# PP-Rev1.net
KiCad netlist of a schematic drawn in EAGLE
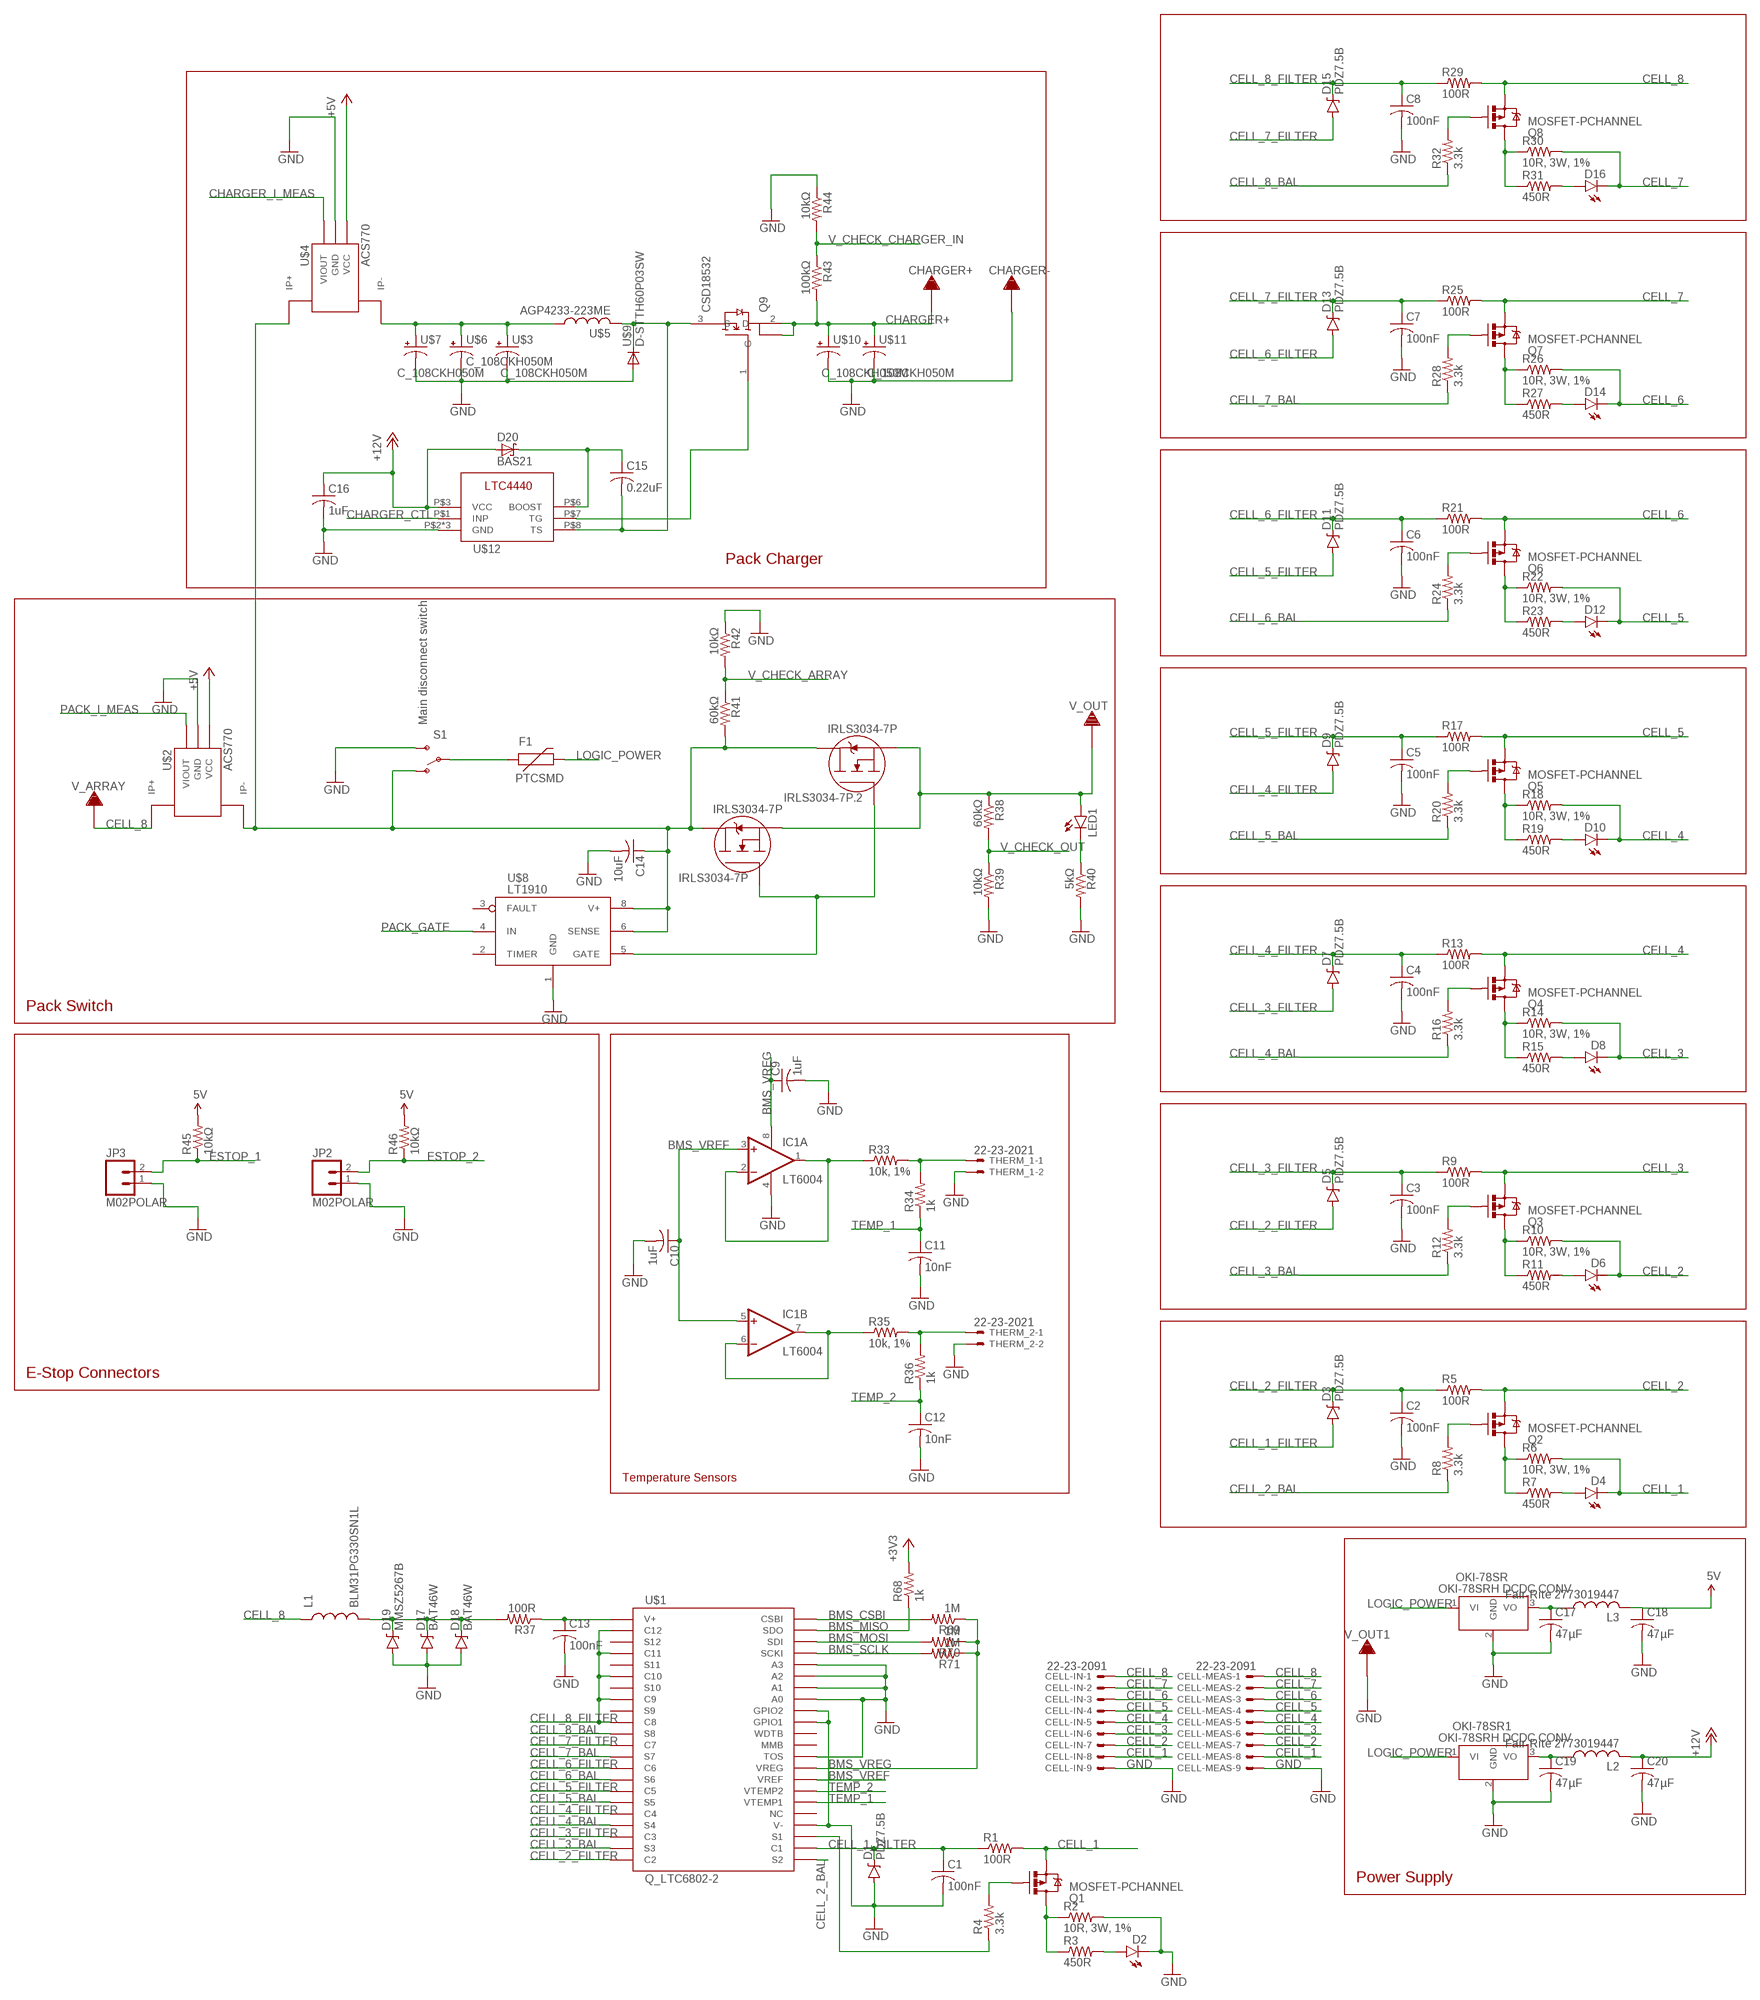
[diagram p0: schematic, sheet 1, part 1 of 2]
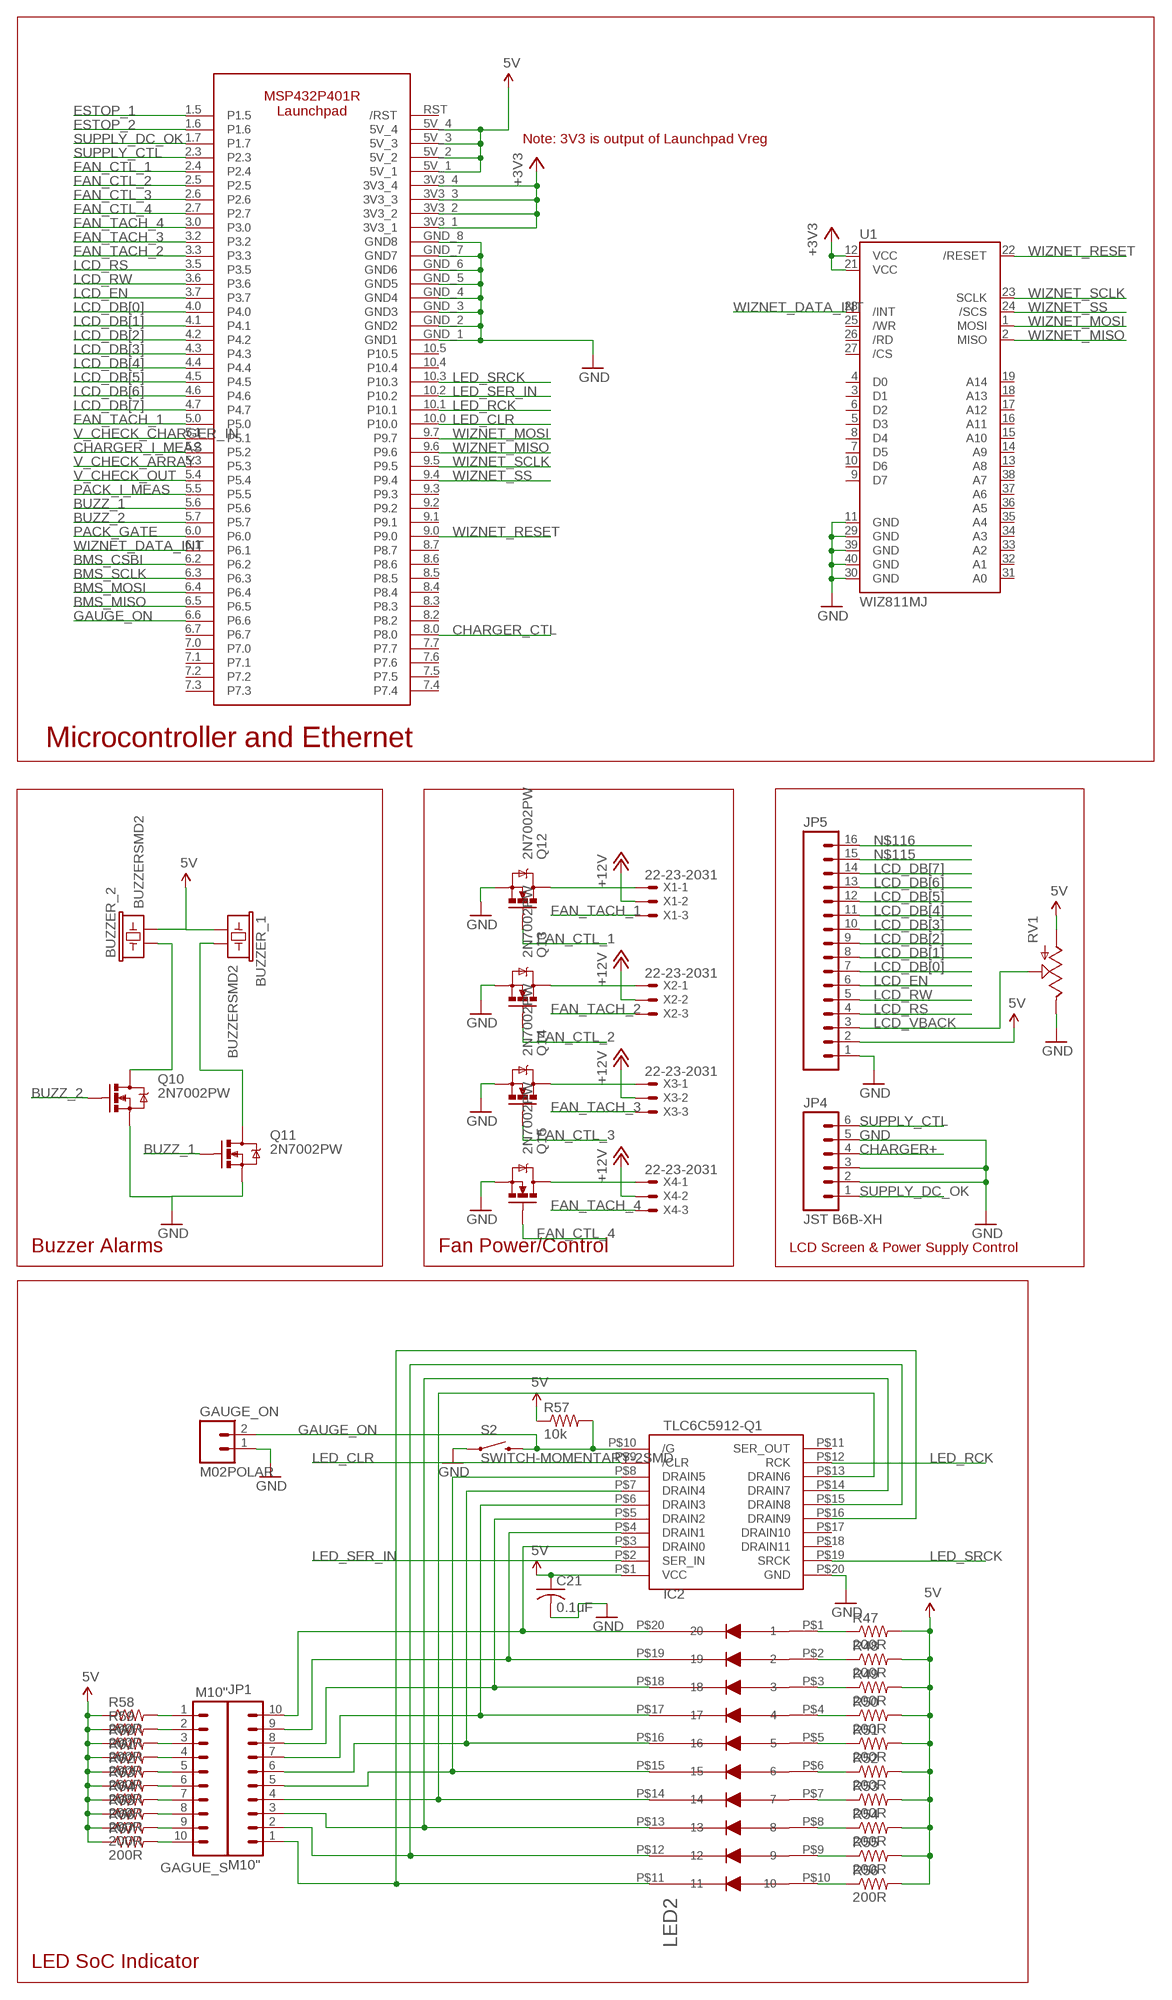
[diagram p1: schematic, sheet 1, part 2 of 2]

(export (version "E")
  (design (tool "Eeschema 10.0.6"))
  (components
    (comp (ref "BUZZER_1")
      (value "BUZZERSMD2")
      (footprint "eagle-import:BUZZER-CCV")
      (libsource (lib "eagle-import") (part "BUZZERSMD2"))
    )
    (comp (ref "BUZZER_2")
      (value "BUZZERSMD2")
      (footprint "eagle-import:BUZZER-CCV")
      (libsource (lib "eagle-import") (part "BUZZERSMD2"))
    )
    (comp (ref "C1")
      (value "100nF")
      (footprint "eagle-import:C1206")
      (libsource (lib "eagle-import") (part "C-USC1206"))
    )
    (comp (ref "C2")
      (value "100nF")
      (footprint "eagle-import:C1206")
      (libsource (lib "eagle-import") (part "C-USC1206"))
    )
    (comp (ref "C3")
      (value "100nF")
      (footprint "eagle-import:C1206")
      (libsource (lib "eagle-import") (part "C-USC1206"))
    )
    (comp (ref "C4")
      (value "100nF")
      (footprint "eagle-import:C1206")
      (libsource (lib "eagle-import") (part "C-USC1206"))
    )
    (comp (ref "C5")
      (value "100nF")
      (footprint "eagle-import:C1206")
      (libsource (lib "eagle-import") (part "C-USC1206"))
    )
    (comp (ref "C6")
      (value "100nF")
      (footprint "eagle-import:C1206")
      (libsource (lib "eagle-import") (part "C-USC1206"))
    )
    (comp (ref "C7")
      (value "100nF")
      (footprint "eagle-import:C1206")
      (libsource (lib "eagle-import") (part "C-USC1206"))
    )
    (comp (ref "C8")
      (value "100nF")
      (footprint "eagle-import:C1206")
      (libsource (lib "eagle-import") (part "C-USC1206"))
    )
    (comp (ref "C9")
      (value "1uF")
      (footprint "eagle-import:C1206")
      (libsource (lib "eagle-import") (part "C-USC1206"))
    )
    (comp (ref "C10")
      (value "1uF")
      (footprint "eagle-import:C1206")
      (libsource (lib "eagle-import") (part "C-USC1206"))
    )
    (comp (ref "C11")
      (value "10nF")
      (footprint "eagle-import:C1206")
      (libsource (lib "eagle-import") (part "C-USC1206"))
    )
    (comp (ref "C12")
      (value "10nF")
      (footprint "eagle-import:C1206")
      (libsource (lib "eagle-import") (part "C-USC1206"))
    )
    (comp (ref "C13")
      (value "100nF")
      (footprint "eagle-import:C1206")
      (libsource (lib "eagle-import") (part "C-USC1206"))
    )
    (comp (ref "C14")
      (value "10uF")
      (footprint "eagle-import:C1206")
      (libsource (lib "eagle-import") (part "C-USC1206"))
    )
    (comp (ref "C15")
      (value "0.22uF")
      (footprint "eagle-import:C1206")
      (libsource (lib "eagle-import") (part "C-USC1206"))
    )
    (comp (ref "C16")
      (value "1uF")
      (footprint "eagle-import:C1206")
      (libsource (lib "eagle-import") (part "C-USC1206"))
    )
    (comp (ref "C17")
      (value "47µF")
      (footprint "eagle-import:C1206")
      (libsource (lib "eagle-import") (part "resistor_C-USC1206"))
    )
    (comp (ref "C18")
      (value "47µF")
      (footprint "eagle-import:C1206")
      (libsource (lib "eagle-import") (part "resistor_C-USC1206"))
    )
    (comp (ref "C19")
      (value "47µF")
      (footprint "eagle-import:C1206")
      (libsource (lib "eagle-import") (part "resistor_C-USC1206"))
    )
    (comp (ref "C20")
      (value "47µF")
      (footprint "eagle-import:C1206")
      (libsource (lib "eagle-import") (part "resistor_C-USC1206"))
    )
    (comp (ref "C21")
      (value "0.1uF")
      (footprint "eagle-import:C1206")
      (libsource (lib "eagle-import") (part "resistor_C-USC1206"))
    )
    (comp (ref "CELL-IN")
      (value "22-23-2091")
      (footprint "eagle-import:22-23-2091")
      (fields (field (name "MF") "MOLEX"))
      (libsource (lib "eagle-import") (part "22-23-2091"))
    )
    (comp (ref "CELL-MEAS")
      (value "22-23-2091")
      (footprint "eagle-import:22-23-2091")
      (fields (field (name "MF") "MOLEX"))
      (libsource (lib "eagle-import") (part "22-23-2091"))
    )
    (comp (ref "CHARGER+")
      (value "TERMINAL_HOLE")
      (footprint "eagle-import:LARGE_TERMINAL_HOLE")
      (libsource (lib "eagle-import") (part "TERMINAL_HOLE"))
    )
    (comp (ref "CHARGER-")
      (value "TERMINAL_HOLE")
      (footprint "eagle-import:LARGE_TERMINAL_HOLE")
      (libsource (lib "eagle-import") (part "TERMINAL_HOLE"))
    )
    (comp (ref "D1")
      (value "PDZ7.5B")
      (footprint "eagle-import:SOD-323")
      (libsource (lib "eagle-import") (part "DIODE-ZENER5.6V"))
    )
    (comp (ref "D2")
      (value "LED1206")
      (footprint "eagle-import:LED-1206")
      (libsource (lib "eagle-import") (part "LED1206"))
    )
    (comp (ref "D3")
      (value "PDZ7.5B")
      (footprint "eagle-import:SOD-323")
      (libsource (lib "eagle-import") (part "DIODE-ZENER5.6V"))
    )
    (comp (ref "D4")
      (value "LED1206")
      (footprint "eagle-import:LED-1206")
      (libsource (lib "eagle-import") (part "LED1206"))
    )
    (comp (ref "D5")
      (value "PDZ7.5B")
      (footprint "eagle-import:SOD-323")
      (libsource (lib "eagle-import") (part "DIODE-ZENER5.6V"))
    )
    (comp (ref "D6")
      (value "LED1206")
      (footprint "eagle-import:LED-1206")
      (libsource (lib "eagle-import") (part "LED1206"))
    )
    (comp (ref "D7")
      (value "PDZ7.5B")
      (footprint "eagle-import:SOD-323")
      (libsource (lib "eagle-import") (part "DIODE-ZENER5.6V"))
    )
    (comp (ref "D8")
      (value "LED1206")
      (footprint "eagle-import:LED-1206")
      (libsource (lib "eagle-import") (part "LED1206"))
    )
    (comp (ref "D9")
      (value "PDZ7.5B")
      (footprint "eagle-import:SOD-323")
      (libsource (lib "eagle-import") (part "DIODE-ZENER5.6V"))
    )
    (comp (ref "D10")
      (value "LED1206")
      (footprint "eagle-import:LED-1206")
      (libsource (lib "eagle-import") (part "LED1206"))
    )
    (comp (ref "D11")
      (value "PDZ7.5B")
      (footprint "eagle-import:SOD-323")
      (libsource (lib "eagle-import") (part "DIODE-ZENER5.6V"))
    )
    (comp (ref "D12")
      (value "LED1206")
      (footprint "eagle-import:LED-1206")
      (libsource (lib "eagle-import") (part "LED1206"))
    )
    (comp (ref "D13")
      (value "PDZ7.5B")
      (footprint "eagle-import:SOD-323")
      (libsource (lib "eagle-import") (part "DIODE-ZENER5.6V"))
    )
    (comp (ref "D14")
      (value "LED1206")
      (footprint "eagle-import:LED-1206")
      (libsource (lib "eagle-import") (part "LED1206"))
    )
    (comp (ref "D15")
      (value "PDZ7.5B")
      (footprint "eagle-import:SOD-323")
      (libsource (lib "eagle-import") (part "DIODE-ZENER5.6V"))
    )
    (comp (ref "D16")
      (value "LED1206")
      (footprint "eagle-import:LED-1206")
      (libsource (lib "eagle-import") (part "LED1206"))
    )
    (comp (ref "D17")
      (value "BAT46W")
      (footprint "eagle-import:SOD-123")
      (libsource (lib "eagle-import") (part "DIODE-ZENER16V"))
    )
    (comp (ref "D18")
      (value "BAT46W")
      (footprint "eagle-import:SOD-123")
      (libsource (lib "eagle-import") (part "DIODE-ZENER16V"))
    )
    (comp (ref "D19")
      (value "MMSZ5267B")
      (footprint "eagle-import:SOD-123")
      (libsource (lib "eagle-import") (part "DIODE-ZENER16V"))
    )
    (comp (ref "D20")
      (value "BAS21")
      (footprint "eagle-import:SOT23")
      (libsource (lib "eagle-import") (part "BAS40"))
    )
    (comp (ref "F1")
      (value "PTCSMD")
      (footprint "eagle-import:PTC-1206")
      (libsource (lib "eagle-import") (part "PTCSMD"))
    )
    (comp (ref "GAGUE_S")
      (value "M10\"")
      (footprint "eagle-import:1X10")
      (libsource (lib "eagle-import") (part "M10{dblquote}"))
    )
    (comp (ref "GAUGE_ON")
      (value "M02POLAR")
      (footprint "eagle-import:MOLEX-1X2")
      (libsource (lib "eagle-import") (part "M02POLAR"))
    )
    (comp (ref "IC1")
      (value "LT6004")
      (footprint "eagle-import:MSOP08")
      (libsource (lib "eagle-import") (part "OPA2E345"))
    )
    (comp (ref "IC2")
      (value "TLC6C5912-Q1")
      (footprint "eagle-import:SOIC-20")
      (libsource (lib "eagle-import") (part "TLC6C5912-Q1"))
    )
    (comp (ref "IRLS3034-7P")
      (value "IRLS3034-7P")
      (footprint "eagle-import:D2PAK-7")
      (libsource (lib "eagle-import") (part "IRLS3034-7P"))
    )
    (comp (ref "IRLS3034-7P.2")
      (value "IRLS3034-7P")
      (footprint "eagle-import:D2PAK-7")
      (libsource (lib "eagle-import") (part "IRLS3034-7P"))
    )
    (comp (ref "JP1")
      (value "M10\"")
      (footprint "eagle-import:1X10")
      (libsource (lib "eagle-import") (part "M10{dblquote}"))
    )
    (comp (ref "JP2")
      (value "M02POLAR")
      (footprint "eagle-import:MOLEX-1X2")
      (libsource (lib "eagle-import") (part "M02POLAR"))
    )
    (comp (ref "JP3")
      (value "M02POLAR")
      (footprint "eagle-import:MOLEX-1X2")
      (libsource (lib "eagle-import") (part "M02POLAR"))
    )
    (comp (ref "JP4")
      (value "JST B6B-XH")
      (footprint "eagle-import:MOLEX-1X6")
      (libsource (lib "eagle-import") (part "M06POLAR"))
    )
    (comp (ref "JP5")
      (value "M16LONGPADS")
      (footprint "eagle-import:1X16_LONGPADS")
      (libsource (lib "eagle-import") (part "M16LONGPADS"))
    )
    (comp (ref "L1")
      (value "BLM31PG330SN1L")
      (footprint "eagle-import:1210")
      (libsource (lib "eagle-import") (part "INDUCTOR1210"))
    )
    (comp (ref "L2")
      (value "Fair-Rite 2773019447")
      (footprint "eagle-import:L8530M")
      (libsource (lib "eagle-import") (part "L-USL8530M"))
    )
    (comp (ref "L3")
      (value "Fair-Rite 2773019447")
      (footprint "eagle-import:L8530M")
      (libsource (lib "eagle-import") (part "L-USL8530M"))
    )
    (comp (ref "LED1")
      (value "LED1206")
      (footprint "eagle-import:LED-1206")
      (libsource (lib "eagle-import") (part "LED1206"))
    )
    (comp (ref "LED2")
      (value "LED-DC7G3HWA")
      (footprint "eagle-import:LED-10")
      (libsource (lib "eagle-import") (part "LED-DC7G3HWA"))
    )
    (comp (ref "OKI-78SR")
      (value "Q_OKI-78SR5")
      (footprint "eagle-import:OKI-78SRH")
      (libsource (lib "eagle-import") (part "Q_OKI-78SR"))
    )
    (comp (ref "OKI-78SR1")
      (value "Q_OKI-78SR12")
      (footprint "eagle-import:OKI-78SRH")
      (libsource (lib "eagle-import") (part "Q_OKI-78SR"))
    )
    (comp (ref "Q1")
      (value "MOSFET-PCHANNEL")
      (footprint "eagle-import:SOT23-3")
      (libsource (lib "eagle-import") (part "MOSFET-PCHANNEL"))
    )
    (comp (ref "Q2")
      (value "MOSFET-PCHANNEL")
      (footprint "eagle-import:SOT23-3")
      (libsource (lib "eagle-import") (part "MOSFET-PCHANNEL"))
    )
    (comp (ref "Q3")
      (value "MOSFET-PCHANNEL")
      (footprint "eagle-import:SOT23-3")
      (libsource (lib "eagle-import") (part "MOSFET-PCHANNEL"))
    )
    (comp (ref "Q4")
      (value "MOSFET-PCHANNEL")
      (footprint "eagle-import:SOT23-3")
      (libsource (lib "eagle-import") (part "MOSFET-PCHANNEL"))
    )
    (comp (ref "Q5")
      (value "MOSFET-PCHANNEL")
      (footprint "eagle-import:SOT23-3")
      (libsource (lib "eagle-import") (part "MOSFET-PCHANNEL"))
    )
    (comp (ref "Q6")
      (value "MOSFET-PCHANNEL")
      (footprint "eagle-import:SOT23-3")
      (libsource (lib "eagle-import") (part "MOSFET-PCHANNEL"))
    )
    (comp (ref "Q7")
      (value "MOSFET-PCHANNEL")
      (footprint "eagle-import:SOT23-3")
      (libsource (lib "eagle-import") (part "MOSFET-PCHANNEL"))
    )
    (comp (ref "Q8")
      (value "MOSFET-PCHANNEL")
      (footprint "eagle-import:SOT23-3")
      (libsource (lib "eagle-import") (part "MOSFET-PCHANNEL"))
    )
    (comp (ref "Q9")
      (value "CSD18532")
      (footprint "eagle-import:TO-220-FLAT")
      (libsource (lib "eagle-import") (part "Q_CSD18532KCSPCB"))
    )
    (comp (ref "Q10")
      (value "2N7002PW")
      (footprint "eagle-import:SOT323")
      (libsource (lib "eagle-import") (part "MOSFET-NCHANNEL2N7002PW"))
    )
    (comp (ref "Q11")
      (value "2N7002PW")
      (footprint "eagle-import:SOT323")
      (libsource (lib "eagle-import") (part "MOSFET-NCHANNEL2N7002PW"))
    )
    (comp (ref "Q12")
      (value "2N7002PW")
      (footprint "eagle-import:SOT323")
      (libsource (lib "eagle-import") (part "MOSFET-NCHANNEL2N7002PW"))
    )
    (comp (ref "Q13")
      (value "2N7002PW")
      (footprint "eagle-import:SOT323")
      (libsource (lib "eagle-import") (part "MOSFET-NCHANNEL2N7002PW"))
    )
    (comp (ref "Q14")
      (value "2N7002PW")
      (footprint "eagle-import:SOT323")
      (libsource (lib "eagle-import") (part "MOSFET-NCHANNEL2N7002PW"))
    )
    (comp (ref "Q15")
      (value "2N7002PW")
      (footprint "eagle-import:SOT323")
      (libsource (lib "eagle-import") (part "MOSFET-NCHANNEL2N7002PW"))
    )
    (comp (ref "R1")
      (value "100R")
      (footprint "eagle-import:R1206")
      (libsource (lib "eagle-import") (part "R-US_R1206"))
    )
    (comp (ref "R2")
      (value "10R, 3W, 1%")
      (footprint "eagle-import:AXIAL-0.6")
      (libsource (lib "eagle-import") (part "RESISTORPTH-1W"))
    )
    (comp (ref "R3")
      (value "450R")
      (footprint "eagle-import:1206")
      (libsource (lib "eagle-import") (part "RESISTOR1206"))
    )
    (comp (ref "R4")
      (value "3.3k")
      (footprint "eagle-import:1206")
      (libsource (lib "eagle-import") (part "RESISTOR1206"))
    )
    (comp (ref "R5")
      (value "100R")
      (footprint "eagle-import:R1206")
      (libsource (lib "eagle-import") (part "R-US_R1206"))
    )
    (comp (ref "R6")
      (value "10R, 3W, 1%")
      (footprint "eagle-import:AXIAL-0.6")
      (libsource (lib "eagle-import") (part "RESISTORPTH-1W"))
    )
    (comp (ref "R7")
      (value "450R")
      (footprint "eagle-import:1206")
      (libsource (lib "eagle-import") (part "RESISTOR1206"))
    )
    (comp (ref "R8")
      (value "3.3k")
      (footprint "eagle-import:1206")
      (libsource (lib "eagle-import") (part "RESISTOR1206"))
    )
    (comp (ref "R9")
      (value "100R")
      (footprint "eagle-import:R1206")
      (libsource (lib "eagle-import") (part "R-US_R1206"))
    )
    (comp (ref "R10")
      (value "10R, 3W, 1%")
      (footprint "eagle-import:AXIAL-0.6")
      (libsource (lib "eagle-import") (part "RESISTORPTH-1W"))
    )
    (comp (ref "R11")
      (value "450R")
      (footprint "eagle-import:1206")
      (libsource (lib "eagle-import") (part "RESISTOR1206"))
    )
    (comp (ref "R12")
      (value "3.3k")
      (footprint "eagle-import:1206")
      (libsource (lib "eagle-import") (part "RESISTOR1206"))
    )
    (comp (ref "R13")
      (value "100R")
      (footprint "eagle-import:R1206")
      (libsource (lib "eagle-import") (part "R-US_R1206"))
    )
    (comp (ref "R14")
      (value "10R, 3W, 1%")
      (footprint "eagle-import:AXIAL-0.6")
      (libsource (lib "eagle-import") (part "RESISTORPTH-1W"))
    )
    (comp (ref "R15")
      (value "450R")
      (footprint "eagle-import:1206")
      (libsource (lib "eagle-import") (part "RESISTOR1206"))
    )
    (comp (ref "R16")
      (value "3.3k")
      (footprint "eagle-import:1206")
      (libsource (lib "eagle-import") (part "RESISTOR1206"))
    )
    (comp (ref "R17")
      (value "100R")
      (footprint "eagle-import:R1206")
      (libsource (lib "eagle-import") (part "R-US_R1206"))
    )
    (comp (ref "R18")
      (value "10R, 3W, 1%")
      (footprint "eagle-import:AXIAL-0.6")
      (libsource (lib "eagle-import") (part "RESISTORPTH-1W"))
    )
    (comp (ref "R19")
      (value "450R")
      (footprint "eagle-import:1206")
      (libsource (lib "eagle-import") (part "RESISTOR1206"))
    )
    (comp (ref "R20")
      (value "3.3k")
      (footprint "eagle-import:1206")
      (libsource (lib "eagle-import") (part "RESISTOR1206"))
    )
    (comp (ref "R21")
      (value "100R")
      (footprint "eagle-import:R1206")
      (libsource (lib "eagle-import") (part "R-US_R1206"))
    )
    (comp (ref "R22")
      (value "10R, 3W, 1%")
      (footprint "eagle-import:AXIAL-0.6")
      (libsource (lib "eagle-import") (part "RESISTORPTH-1W"))
    )
    (comp (ref "R23")
      (value "450R")
      (footprint "eagle-import:1206")
      (libsource (lib "eagle-import") (part "RESISTOR1206"))
    )
    (comp (ref "R24")
      (value "3.3k")
      (footprint "eagle-import:1206")
      (libsource (lib "eagle-import") (part "RESISTOR1206"))
    )
    (comp (ref "R25")
      (value "100R")
      (footprint "eagle-import:R1206")
      (libsource (lib "eagle-import") (part "R-US_R1206"))
    )
    (comp (ref "R26")
      (value "10R, 3W, 1%")
      (footprint "eagle-import:AXIAL-0.6")
      (libsource (lib "eagle-import") (part "RESISTORPTH-1W"))
    )
    (comp (ref "R27")
      (value "450R")
      (footprint "eagle-import:1206")
      (libsource (lib "eagle-import") (part "RESISTOR1206"))
    )
    (comp (ref "R28")
      (value "3.3k")
      (footprint "eagle-import:1206")
      (libsource (lib "eagle-import") (part "RESISTOR1206"))
    )
    (comp (ref "R29")
      (value "100R")
      (footprint "eagle-import:R1206")
      (libsource (lib "eagle-import") (part "R-US_R1206"))
    )
    (comp (ref "R30")
      (value "10R, 3W, 1%")
      (footprint "eagle-import:AXIAL-0.6")
      (libsource (lib "eagle-import") (part "RESISTORPTH-1W"))
    )
    (comp (ref "R31")
      (value "450R")
      (footprint "eagle-import:1206")
      (libsource (lib "eagle-import") (part "RESISTOR1206"))
    )
    (comp (ref "R32")
      (value "3.3k")
      (footprint "eagle-import:1206")
      (libsource (lib "eagle-import") (part "RESISTOR1206"))
    )
    (comp (ref "R33")
      (value "10k, 1%")
      (footprint "eagle-import:R1206")
      (libsource (lib "eagle-import") (part "R-US_R1206"))
    )
    (comp (ref "R34")
      (value "1k")
      (footprint "eagle-import:R1206")
      (libsource (lib "eagle-import") (part "R-US_R1206"))
    )
    (comp (ref "R35")
      (value "10k, 1%")
      (footprint "eagle-import:R1206")
      (libsource (lib "eagle-import") (part "R-US_R1206"))
    )
    (comp (ref "R36")
      (value "1k")
      (footprint "eagle-import:R1206")
      (libsource (lib "eagle-import") (part "R-US_R1206"))
    )
    (comp (ref "R37")
      (value "100R")
      (footprint "eagle-import:R1206")
      (libsource (lib "eagle-import") (part "R-US_R1206"))
    )
    (comp (ref "R38")
      (value "60kΩ")
      (footprint "eagle-import:R1206")
      (libsource (lib "eagle-import") (part "resistor_R-US_R1206"))
    )
    (comp (ref "R39")
      (value "10kΩ")
      (footprint "eagle-import:R1206")
      (libsource (lib "eagle-import") (part "resistor_R-US_R1206"))
    )
    (comp (ref "R40")
      (value "5kΩ")
      (footprint "eagle-import:R1206")
      (libsource (lib "eagle-import") (part "resistor_R-US_R1206"))
    )
    (comp (ref "R41")
      (value "60kΩ")
      (footprint "eagle-import:R1206")
      (libsource (lib "eagle-import") (part "resistor_R-US_R1206"))
    )
    (comp (ref "R42")
      (value "10kΩ")
      (footprint "eagle-import:R1206")
      (libsource (lib "eagle-import") (part "resistor_R-US_R1206"))
    )
    (comp (ref "R43")
      (value "100kΩ")
      (footprint "eagle-import:R1206")
      (libsource (lib "eagle-import") (part "resistor_R-US_R1206"))
    )
    (comp (ref "R44")
      (value "10kΩ")
      (footprint "eagle-import:R1206")
      (libsource (lib "eagle-import") (part "resistor_R-US_R1206"))
    )
    (comp (ref "R45")
      (value "10kΩ")
      (footprint "eagle-import:R1206")
      (libsource (lib "eagle-import") (part "resistor_R-US_R1206"))
    )
    (comp (ref "R46")
      (value "10kΩ")
      (footprint "eagle-import:R1206")
      (libsource (lib "eagle-import") (part "resistor_R-US_R1206"))
    )
    (comp (ref "R47")
      (value "200R")
      (footprint "eagle-import:R1206")
      (libsource (lib "eagle-import") (part "R-US_R1206"))
    )
    (comp (ref "R48")
      (value "200R")
      (footprint "eagle-import:R1206")
      (libsource (lib "eagle-import") (part "R-US_R1206"))
    )
    (comp (ref "R49")
      (value "200R")
      (footprint "eagle-import:R1206")
      (libsource (lib "eagle-import") (part "R-US_R1206"))
    )
    (comp (ref "R50")
      (value "200R")
      (footprint "eagle-import:R1206")
      (libsource (lib "eagle-import") (part "R-US_R1206"))
    )
    (comp (ref "R51")
      (value "200R")
      (footprint "eagle-import:R1206")
      (libsource (lib "eagle-import") (part "R-US_R1206"))
    )
    (comp (ref "R52")
      (value "200R")
      (footprint "eagle-import:R1206")
      (libsource (lib "eagle-import") (part "R-US_R1206"))
    )
    (comp (ref "R53")
      (value "200R")
      (footprint "eagle-import:R1206")
      (libsource (lib "eagle-import") (part "R-US_R1206"))
    )
    (comp (ref "R54")
      (value "200R")
      (footprint "eagle-import:R1206")
      (libsource (lib "eagle-import") (part "R-US_R1206"))
    )
    (comp (ref "R55")
      (value "200R")
      (footprint "eagle-import:R1206")
      (libsource (lib "eagle-import") (part "R-US_R1206"))
    )
    (comp (ref "R56")
      (value "200R")
      (footprint "eagle-import:R1206")
      (libsource (lib "eagle-import") (part "R-US_R1206"))
    )
    (comp (ref "R57")
      (value "10k")
      (footprint "eagle-import:R1206")
      (libsource (lib "eagle-import") (part "R-US_R1206"))
    )
    (comp (ref "R58")
      (value "200R")
      (footprint "eagle-import:R1206")
      (libsource (lib "eagle-import") (part "R-US_R1206"))
    )
    (comp (ref "R59")
      (value "200R")
      (footprint "eagle-import:R1206")
      (libsource (lib "eagle-import") (part "R-US_R1206"))
    )
    (comp (ref "R60")
      (value "200R")
      (footprint "eagle-import:R1206")
      (libsource (lib "eagle-import") (part "R-US_R1206"))
    )
    (comp (ref "R61")
      (value "200R")
      (footprint "eagle-import:R1206")
      (libsource (lib "eagle-import") (part "R-US_R1206"))
    )
    (comp (ref "R62")
      (value "200R")
      (footprint "eagle-import:R1206")
      (libsource (lib "eagle-import") (part "R-US_R1206"))
    )
    (comp (ref "R63")
      (value "200R")
      (footprint "eagle-import:R1206")
      (libsource (lib "eagle-import") (part "R-US_R1206"))
    )
    (comp (ref "R64")
      (value "200R")
      (footprint "eagle-import:R1206")
      (libsource (lib "eagle-import") (part "R-US_R1206"))
    )
    (comp (ref "R65")
      (value "200R")
      (footprint "eagle-import:R1206")
      (libsource (lib "eagle-import") (part "R-US_R1206"))
    )
    (comp (ref "R66")
      (value "200R")
      (footprint "eagle-import:R1206")
      (libsource (lib "eagle-import") (part "R-US_R1206"))
    )
    (comp (ref "R67")
      (value "200R")
      (footprint "eagle-import:R1206")
      (libsource (lib "eagle-import") (part "R-US_R1206"))
    )
    (comp (ref "R68")
      (value "1k")
      (footprint "eagle-import:R1206")
      (libsource (lib "eagle-import") (part "R-US_R1206"))
    )
    (comp (ref "R69")
      (value "1M")
      (footprint "eagle-import:R1206")
      (libsource (lib "eagle-import") (part "R-US_R1206"))
    )
    (comp (ref "R70")
      (value "1M")
      (footprint "eagle-import:R1206")
      (libsource (lib "eagle-import") (part "R-US_R1206"))
    )
    (comp (ref "R71")
      (value "1M")
      (footprint "eagle-import:R1206")
      (libsource (lib "eagle-import") (part "R-US_R1206"))
    )
    (comp (ref "RV1")
      (value "POTTRIM")
      (footprint "eagle-import:TRIM_POT")
      (libsource (lib "eagle-import") (part "POTTRIM"))
    )
    (comp (ref "S1")
      (value "SWITCH-SPDTPTH")
      (footprint "eagle-import:SWITCH-SPDT")
      (libsource (lib "eagle-import") (part "SWITCH-SPDTPTH"))
    )
    (comp (ref "S2")
      (value "SWITCH-MOMENTARY-2SMD")
      (footprint "eagle-import:TACTILE-SWITCH-SMD")
      (libsource (lib "eagle-import") (part "SWITCH-MOMENTARY-2SMD"))
    )
    (comp (ref "THERM_1")
      (value "22-23-2021")
      (footprint "eagle-import:22-23-2021")
      (fields (field (name "MF") "MOLEX"))
      (libsource (lib "eagle-import") (part "22-23-2021"))
    )
    (comp (ref "THERM_2")
      (value "22-23-2021")
      (footprint "eagle-import:22-23-2021")
      (fields (field (name "MF") "MOLEX"))
      (libsource (lib "eagle-import") (part "22-23-2021"))
    )
    (comp (ref "U$1")
      (value "Q_LTC6802-2")
      (footprint "eagle-import:SSOP44")
      (libsource (lib "eagle-import") (part "Q_LTC6802-2"))
    )
    (comp (ref "U$2")
      (value "ACS770")
      (footprint "eagle-import:PFF_LEADFORM")
      (libsource (lib "eagle-import") (part "ACS770"))
    )
    (comp (ref "U$3")
      (value "C_108CKH050M")
      (footprint "eagle-import:C_16MM")
      (libsource (lib "eagle-import") (part "C_108CKH050M"))
    )
    (comp (ref "U$4")
      (value "ACS770")
      (footprint "eagle-import:PFF_LEADFORM")
      (libsource (lib "eagle-import") (part "ACS770"))
    )
    (comp (ref "U$5")
      (value "AGP4233-223ME")
      (footprint "eagle-import:AGP4233")
      (libsource (lib "eagle-import") (part "AGP4233"))
    )
    (comp (ref "U$6")
      (value "C_108CKH050M")
      (footprint "eagle-import:C_16MM")
      (libsource (lib "eagle-import") (part "C_108CKH050M"))
    )
    (comp (ref "U$7")
      (value "C_108CKH050M")
      (footprint "eagle-import:C_16MM")
      (libsource (lib "eagle-import") (part "C_108CKH050M"))
    )
    (comp (ref "U$8")
      (value "LT1910")
      (footprint "eagle-import:SO8")
      (libsource (lib "eagle-import") (part "LT1910"))
    )
    (comp (ref "U$9")
      (value "D-STTH60P03SW")
      (footprint "eagle-import:TO-247-VERT")
      (libsource (lib "eagle-import") (part "D-STTH60P03SW"))
    )
    (comp (ref "U$10")
      (value "C_108CKH050M")
      (footprint "eagle-import:C_16MM")
      (libsource (lib "eagle-import") (part "C_108CKH050M"))
    )
    (comp (ref "U$11")
      (value "C_108CKH050M")
      (footprint "eagle-import:C_16MM")
      (libsource (lib "eagle-import") (part "C_108CKH050M"))
    )
    (comp (ref "U$12")
      (value "LTC4440")
      (footprint "eagle-import:MS8E")
      (libsource (lib "eagle-import") (part "LTC4440"))
    )
    (comp (ref "U$13")
      (value "MSP432P401R-LAUNCHPAD")
      (footprint "eagle-import:MSP432P401R-LAUNCHPAD")
      (libsource (lib "eagle-import") (part "MSP432P401R-LAUNCHPAD"))
    )
    (comp (ref "U1")
      (value "WIZ811MJ")
      (footprint "eagle-import:WIZ811MJ")
      (libsource (lib "eagle-import") (part "WIZ811MJ"))
    )
    (comp (ref "V_ARRAY")
      (value "TERMINAL_HOLE")
      (footprint "eagle-import:LARGE_TERMINAL_HOLE")
      (libsource (lib "eagle-import") (part "TERMINAL_HOLE"))
    )
    (comp (ref "V_OUT")
      (value "TERMINAL_HOLE")
      (footprint "eagle-import:LARGE_TERMINAL_HOLE")
      (libsource (lib "eagle-import") (part "TERMINAL_HOLE"))
    )
    (comp (ref "V_OUT1")
      (value "TERMINAL_HOLE")
      (footprint "eagle-import:LARGE_TERMINAL_HOLE")
      (libsource (lib "eagle-import") (part "TERMINAL_HOLE"))
    )
    (comp (ref "X1")
      (value "22-23-2031")
      (footprint "eagle-import:22-23-2031")
      (fields (field (name "MF") "MOLEX"))
      (libsource (lib "eagle-import") (part "22-23-2031"))
    )
    (comp (ref "X2")
      (value "22-23-2031")
      (footprint "eagle-import:22-23-2031")
      (fields (field (name "MF") "MOLEX"))
      (libsource (lib "eagle-import") (part "22-23-2031"))
    )
    (comp (ref "X3")
      (value "22-23-2031")
      (footprint "eagle-import:22-23-2031")
      (fields (field (name "MF") "MOLEX"))
      (libsource (lib "eagle-import") (part "22-23-2031"))
    )
    (comp (ref "X4")
      (value "22-23-2031")
      (footprint "eagle-import:22-23-2031")
      (fields (field (name "MF") "MOLEX"))
      (libsource (lib "eagle-import") (part "22-23-2031"))
    )
  )
  (nets
    (net (code "1") (name "+3V3") (class "Default")
      (node (ref "R68") (pin "2") (pinfunction "2_2") (pintype "passive"))
      (node (ref "U$13") (pin "3V3_1") (pinfunction "3V3_1_3V3_1") (pintype "bidirectional"))
      (node (ref "U$13") (pin "3V3_2") (pinfunction "3V3_2_3V3_2") (pintype "bidirectional"))
      (node (ref "U$13") (pin "3V3_3") (pinfunction "3V3_3_3V3_3") (pintype "bidirectional"))
      (node (ref "U$13") (pin "3V3_4") (pinfunction "3V3_4_3V3_4") (pintype "bidirectional"))
      (node (ref "U1") (pin "12") (pinfunction "VCC_12") (pintype "bidirectional"))
      (node (ref "U1") (pin "21") (pinfunction "VCC_21") (pintype "bidirectional"))
    )
    (net (code "2") (name "+5V") (class "Default")
      (node (ref "U$2") (pin "1") (pinfunction "VCC_1") (pintype "bidirectional"))
      (node (ref "U$4") (pin "1") (pinfunction "VCC_1") (pintype "bidirectional"))
    )
    (net (code "3") (name "+12V") (class "Default")
      (node (ref "C16") (pin "1") (pinfunction "1_1") (pintype "passive"))
      (node (ref "C20") (pin "1") (pinfunction "1_1") (pintype "passive"))
      (node (ref "D20") (pin "1") (pinfunction "A_1") (pintype "passive"))
      (node (ref "L2") (pin "2") (pinfunction "2_2") (pintype "passive"))
      (node (ref "U$12") (pin "P$3") (pinfunction "VCC_P$3") (pintype "bidirectional"))
      (node (ref "X1") (pin "2") (pinfunction "S_2") (pintype "passive"))
      (node (ref "X2") (pin "2") (pinfunction "S_2") (pintype "passive"))
      (node (ref "X3") (pin "2") (pinfunction "S_2") (pintype "passive"))
      (node (ref "X4") (pin "2") (pinfunction "S_2") (pintype "passive"))
    )
    (net (code "4") (name "/BMS_CSBI") (class "Default")
      (node (ref "R69") (pin "2") (pinfunction "2_2") (pintype "passive"))
      (node (ref "U$1") (pin "44") (pinfunction "CSBI_44") (pintype "bidirectional"))
      (node (ref "U$13") (pin "6.2") (pinfunction "P6.2_6.2") (pintype "bidirectional"))
    )
    (net (code "5") (name "/BMS_MISO") (class "Default")
      (node (ref "R68") (pin "1") (pinfunction "1_1") (pintype "passive"))
      (node (ref "U$1") (pin "43") (pinfunction "SDO_43") (pintype "bidirectional"))
      (node (ref "U$13") (pin "6.5") (pinfunction "P6.5_6.5") (pintype "bidirectional"))
    )
    (net (code "6") (name "/BMS_MOSI") (class "Default")
      (node (ref "R70") (pin "2") (pinfunction "2_2") (pintype "passive"))
      (node (ref "U$1") (pin "42") (pinfunction "SDI_42") (pintype "bidirectional"))
      (node (ref "U$13") (pin "6.4") (pinfunction "P6.4_6.4") (pintype "bidirectional"))
    )
    (net (code "7") (name "/BMS_SCLK") (class "Default")
      (node (ref "R71") (pin "2") (pinfunction "2_2") (pintype "passive"))
      (node (ref "U$1") (pin "41") (pinfunction "SCKI_41") (pintype "bidirectional"))
      (node (ref "U$13") (pin "6.3") (pinfunction "P6.3_6.3") (pintype "bidirectional"))
    )
    (net (code "8") (name "/BMS_VREF") (class "Default")
      (node (ref "C10") (pin "1") (pinfunction "1_1") (pintype "passive"))
      (node (ref "IC1") (pin "3") (pinfunction "+IN_3") (pintype "input"))
      (node (ref "IC1") (pin "5") (pinfunction "+IN_5") (pintype "input"))
      (node (ref "U$1") (pin "30") (pinfunction "VREF_30") (pintype "bidirectional"))
    )
    (net (code "9") (name "/BMS_VREG") (class "Default")
      (node (ref "C9") (pin "1") (pinfunction "1_1") (pintype "passive"))
      (node (ref "IC1") (pin "8") (pinfunction "V+_8") (pintype "power_in"))
      (node (ref "R69") (pin "1") (pinfunction "1_1") (pintype "passive"))
      (node (ref "R70") (pin "1") (pinfunction "1_1") (pintype "passive"))
      (node (ref "R71") (pin "1") (pinfunction "1_1") (pintype "passive"))
      (node (ref "U$1") (pin "31") (pinfunction "VREG_31") (pintype "bidirectional"))
    )
    (net (code "10") (name "/BUZZ_1") (class "Default")
      (node (ref "Q11") (pin "1") (pinfunction "G_1") (pintype "passive"))
      (node (ref "U$13") (pin "5.6") (pinfunction "P5.6_5.6") (pintype "bidirectional"))
    )
    (net (code "11") (name "/BUZZ_2") (class "Default")
      (node (ref "Q10") (pin "1") (pinfunction "G_1") (pintype "passive"))
      (node (ref "U$13") (pin "5.7") (pinfunction "P5.7_5.7") (pintype "bidirectional"))
    )
    (net (code "12") (name "/CELL_1") (class "Default")
      (node (ref "CELL-IN") (pin "8") (pinfunction "S_8") (pintype "passive"))
      (node (ref "CELL-MEAS") (pin "8") (pinfunction "S_8") (pintype "passive"))
      (node (ref "D4") (pin "C") (pinfunction "C_C") (pintype "passive"))
      (node (ref "Q1") (pin "2") (pinfunction "S_2") (pintype "passive"))
      (node (ref "R1") (pin "2") (pinfunction "2_2") (pintype "passive"))
      (node (ref "R6") (pin "P$2") (pinfunction "2_P$2") (pintype "passive"))
    )
    (net (code "13") (name "/CELL_1_FILTER") (class "Default")
      (node (ref "C1") (pin "1") (pinfunction "1_1") (pintype "passive"))
      (node (ref "D1") (pin "C") (pinfunction "C_C") (pintype "passive"))
      (node (ref "D3") (pin "A") (pinfunction "A_A") (pintype "passive"))
      (node (ref "R1") (pin "1") (pinfunction "1_1") (pintype "passive"))
      (node (ref "U$1") (pin "24") (pinfunction "C1_24") (pintype "bidirectional"))
    )
    (net (code "14") (name "/CELL_2") (class "Default")
      (node (ref "CELL-IN") (pin "7") (pinfunction "S_7") (pintype "passive"))
      (node (ref "CELL-MEAS") (pin "7") (pinfunction "S_7") (pintype "passive"))
      (node (ref "D6") (pin "C") (pinfunction "C_C") (pintype "passive"))
      (node (ref "Q2") (pin "2") (pinfunction "S_2") (pintype "passive"))
      (node (ref "R10") (pin "P$2") (pinfunction "2_P$2") (pintype "passive"))
      (node (ref "R5") (pin "2") (pinfunction "2_2") (pintype "passive"))
    )
    (net (code "15") (name "/CELL_2_BAL") (class "Default")
      (node (ref "R8") (pin "1") (pinfunction "1_1") (pintype "passive"))
      (node (ref "U$1") (pin "23") (pinfunction "S2_23") (pintype "bidirectional"))
    )
    (net (code "16") (name "/CELL_2_FILTER") (class "Default")
      (node (ref "C2") (pin "1") (pinfunction "1_1") (pintype "passive"))
      (node (ref "D3") (pin "C") (pinfunction "C_C") (pintype "passive"))
      (node (ref "D5") (pin "A") (pinfunction "A_A") (pintype "passive"))
      (node (ref "R5") (pin "1") (pinfunction "1_1") (pintype "passive"))
      (node (ref "U$1") (pin "22") (pinfunction "C2_22") (pintype "bidirectional"))
    )
    (net (code "17") (name "/CELL_3") (class "Default")
      (node (ref "CELL-IN") (pin "6") (pinfunction "S_6") (pintype "passive"))
      (node (ref "CELL-MEAS") (pin "6") (pinfunction "S_6") (pintype "passive"))
      (node (ref "D8") (pin "C") (pinfunction "C_C") (pintype "passive"))
      (node (ref "Q3") (pin "2") (pinfunction "S_2") (pintype "passive"))
      (node (ref "R14") (pin "P$2") (pinfunction "2_P$2") (pintype "passive"))
      (node (ref "R9") (pin "2") (pinfunction "2_2") (pintype "passive"))
    )
    (net (code "18") (name "/CELL_3_BAL") (class "Default")
      (node (ref "R12") (pin "1") (pinfunction "1_1") (pintype "passive"))
      (node (ref "U$1") (pin "21") (pinfunction "S3_21") (pintype "bidirectional"))
    )
    (net (code "19") (name "/CELL_3_FILTER") (class "Default")
      (node (ref "C3") (pin "1") (pinfunction "1_1") (pintype "passive"))
      (node (ref "D5") (pin "C") (pinfunction "C_C") (pintype "passive"))
      (node (ref "D7") (pin "A") (pinfunction "A_A") (pintype "passive"))
      (node (ref "R9") (pin "1") (pinfunction "1_1") (pintype "passive"))
      (node (ref "U$1") (pin "20") (pinfunction "C3_20") (pintype "bidirectional"))
    )
    (net (code "20") (name "/CELL_4") (class "Default")
      (node (ref "CELL-IN") (pin "5") (pinfunction "S_5") (pintype "passive"))
      (node (ref "CELL-MEAS") (pin "5") (pinfunction "S_5") (pintype "passive"))
      (node (ref "D10") (pin "C") (pinfunction "C_C") (pintype "passive"))
      (node (ref "Q4") (pin "2") (pinfunction "S_2") (pintype "passive"))
      (node (ref "R13") (pin "2") (pinfunction "2_2") (pintype "passive"))
      (node (ref "R18") (pin "P$2") (pinfunction "2_P$2") (pintype "passive"))
    )
    (net (code "21") (name "/CELL_4_BAL") (class "Default")
      (node (ref "R16") (pin "1") (pinfunction "1_1") (pintype "passive"))
      (node (ref "U$1") (pin "19") (pinfunction "S4_19") (pintype "bidirectional"))
    )
    (net (code "22") (name "/CELL_4_FILTER") (class "Default")
      (node (ref "C4") (pin "1") (pinfunction "1_1") (pintype "passive"))
      (node (ref "D7") (pin "C") (pinfunction "C_C") (pintype "passive"))
      (node (ref "D9") (pin "A") (pinfunction "A_A") (pintype "passive"))
      (node (ref "R13") (pin "1") (pinfunction "1_1") (pintype "passive"))
      (node (ref "U$1") (pin "18") (pinfunction "C4_18") (pintype "bidirectional"))
    )
    (net (code "23") (name "/CELL_5") (class "Default")
      (node (ref "CELL-IN") (pin "4") (pinfunction "S_4") (pintype "passive"))
      (node (ref "CELL-MEAS") (pin "4") (pinfunction "S_4") (pintype "passive"))
      (node (ref "D12") (pin "C") (pinfunction "C_C") (pintype "passive"))
      (node (ref "Q5") (pin "2") (pinfunction "S_2") (pintype "passive"))
      (node (ref "R17") (pin "2") (pinfunction "2_2") (pintype "passive"))
      (node (ref "R22") (pin "P$2") (pinfunction "2_P$2") (pintype "passive"))
    )
    (net (code "24") (name "/CELL_5_BAL") (class "Default")
      (node (ref "R20") (pin "1") (pinfunction "1_1") (pintype "passive"))
      (node (ref "U$1") (pin "17") (pinfunction "S5_17") (pintype "bidirectional"))
    )
    (net (code "25") (name "/CELL_5_FILTER") (class "Default")
      (node (ref "C5") (pin "1") (pinfunction "1_1") (pintype "passive"))
      (node (ref "D11") (pin "A") (pinfunction "A_A") (pintype "passive"))
      (node (ref "D9") (pin "C") (pinfunction "C_C") (pintype "passive"))
      (node (ref "R17") (pin "1") (pinfunction "1_1") (pintype "passive"))
      (node (ref "U$1") (pin "16") (pinfunction "C5_16") (pintype "bidirectional"))
    )
    (net (code "26") (name "/CELL_6") (class "Default")
      (node (ref "CELL-IN") (pin "3") (pinfunction "S_3") (pintype "passive"))
      (node (ref "CELL-MEAS") (pin "3") (pinfunction "S_3") (pintype "passive"))
      (node (ref "D14") (pin "C") (pinfunction "C_C") (pintype "passive"))
      (node (ref "Q6") (pin "2") (pinfunction "S_2") (pintype "passive"))
      (node (ref "R21") (pin "2") (pinfunction "2_2") (pintype "passive"))
      (node (ref "R26") (pin "P$2") (pinfunction "2_P$2") (pintype "passive"))
    )
    (net (code "27") (name "/CELL_6_BAL") (class "Default")
      (node (ref "R24") (pin "1") (pinfunction "1_1") (pintype "passive"))
      (node (ref "U$1") (pin "15") (pinfunction "S6_15") (pintype "bidirectional"))
    )
    (net (code "28") (name "/CELL_6_FILTER") (class "Default")
      (node (ref "C6") (pin "1") (pinfunction "1_1") (pintype "passive"))
      (node (ref "D11") (pin "C") (pinfunction "C_C") (pintype "passive"))
      (node (ref "D13") (pin "A") (pinfunction "A_A") (pintype "passive"))
      (node (ref "R21") (pin "1") (pinfunction "1_1") (pintype "passive"))
      (node (ref "U$1") (pin "14") (pinfunction "C6_14") (pintype "bidirectional"))
    )
    (net (code "29") (name "/CELL_7") (class "Default")
      (node (ref "CELL-IN") (pin "2") (pinfunction "S_2") (pintype "passive"))
      (node (ref "CELL-MEAS") (pin "2") (pinfunction "S_2") (pintype "passive"))
      (node (ref "D16") (pin "C") (pinfunction "C_C") (pintype "passive"))
      (node (ref "Q7") (pin "2") (pinfunction "S_2") (pintype "passive"))
      (node (ref "R25") (pin "2") (pinfunction "2_2") (pintype "passive"))
      (node (ref "R30") (pin "P$2") (pinfunction "2_P$2") (pintype "passive"))
    )
    (net (code "30") (name "/CELL_7_BAL") (class "Default")
      (node (ref "R28") (pin "1") (pinfunction "1_1") (pintype "passive"))
      (node (ref "U$1") (pin "13") (pinfunction "S7_13") (pintype "bidirectional"))
    )
    (net (code "31") (name "/CELL_7_FILTER") (class "Default")
      (node (ref "C7") (pin "1") (pinfunction "1_1") (pintype "passive"))
      (node (ref "D13") (pin "C") (pinfunction "C_C") (pintype "passive"))
      (node (ref "D15") (pin "A") (pinfunction "A_A") (pintype "passive"))
      (node (ref "R25") (pin "1") (pinfunction "1_1") (pintype "passive"))
      (node (ref "U$1") (pin "12") (pinfunction "C7_12") (pintype "bidirectional"))
    )
    (net (code "32") (name "/CELL_8") (class "Default")
      (node (ref "CELL-IN") (pin "1") (pinfunction "S_1") (pintype "passive"))
      (node (ref "CELL-MEAS") (pin "1") (pinfunction "S_1") (pintype "passive"))
      (node (ref "L1") (pin "1") (pinfunction "1_1") (pintype "passive"))
      (node (ref "Q8") (pin "2") (pinfunction "S_2") (pintype "passive"))
      (node (ref "R29") (pin "2") (pinfunction "2_2") (pintype "passive"))
      (node (ref "U$2") (pin "4_1") (pinfunction "IP+_4_1") (pintype "bidirectional"))
      (node (ref "U$2") (pin "4_10") (pinfunction "IP+_4_10") (pintype "bidirectional"))
      (node (ref "U$2") (pin "4_11") (pinfunction "IP+_4_11") (pintype "bidirectional"))
      (node (ref "U$2") (pin "4_12") (pinfunction "IP+_4_12") (pintype "bidirectional"))
      (node (ref "U$2") (pin "4_13") (pinfunction "IP+_4_13") (pintype "bidirectional"))
      (node (ref "U$2") (pin "4_14") (pinfunction "IP+_4_14") (pintype "bidirectional"))
      (node (ref "U$2") (pin "4_15") (pinfunction "IP+_4_15") (pintype "bidirectional"))
      (node (ref "U$2") (pin "4_16") (pinfunction "IP+_4_16") (pintype "bidirectional"))
      (node (ref "U$2") (pin "4_2") (pinfunction "IP+_4_2") (pintype "bidirectional"))
      (node (ref "U$2") (pin "4_3") (pinfunction "IP+_4_3") (pintype "bidirectional"))
      (node (ref "U$2") (pin "4_4") (pinfunction "IP+_4_4") (pintype "bidirectional"))
      (node (ref "U$2") (pin "4_5") (pinfunction "IP+_4_5") (pintype "bidirectional"))
      (node (ref "U$2") (pin "4_6") (pinfunction "IP+_4_6") (pintype "bidirectional"))
      (node (ref "U$2") (pin "4_7") (pinfunction "IP+_4_7") (pintype "bidirectional"))
      (node (ref "U$2") (pin "4_8") (pinfunction "IP+_4_8") (pintype "bidirectional"))
      (node (ref "U$2") (pin "4_9") (pinfunction "IP+_4_9") (pintype "bidirectional"))
      (node (ref "U$2") (pin "4_B") (pinfunction "IP+_4_B") (pintype "bidirectional"))
      (node (ref "U$2") (pin "4_T") (pinfunction "IP+_4_T") (pintype "bidirectional"))
      (node (ref "V_ARRAY") (pin "P$1") (pinfunction "P$1_P$1") (pintype "bidirectional"))
    )
    (net (code "33") (name "/CELL_8_BAL") (class "Default")
      (node (ref "R32") (pin "1") (pinfunction "1_1") (pintype "passive"))
      (node (ref "U$1") (pin "11") (pinfunction "S8_11") (pintype "bidirectional"))
    )
    (net (code "34") (name "/CELL_8_FILTER") (class "Default")
      (node (ref "C8") (pin "1") (pinfunction "1_1") (pintype "passive"))
      (node (ref "D15") (pin "C") (pinfunction "C_C") (pintype "passive"))
      (node (ref "R29") (pin "1") (pinfunction "1_1") (pintype "passive"))
      (node (ref "U$1") (pin "10") (pinfunction "C8_10") (pintype "bidirectional"))
      (node (ref "U$1") (pin "2") (pinfunction "C12_2") (pintype "bidirectional"))
      (node (ref "U$1") (pin "4") (pinfunction "C11_4") (pintype "bidirectional"))
      (node (ref "U$1") (pin "6") (pinfunction "C10_6") (pintype "bidirectional"))
      (node (ref "U$1") (pin "8") (pinfunction "C9_8") (pintype "bidirectional"))
    )
    (net (code "35") (name "/CHARGER+") (class "Default")
      (node (ref "CHARGER+") (pin "P$1") (pinfunction "P$1_P$1") (pintype "bidirectional"))
      (node (ref "JP4") (pin "4") (pinfunction "4_4") (pintype "passive"))
      (node (ref "Q9") (pin "2") (pinfunction "D_2") (pintype "bidirectional"))
      (node (ref "Q9") (pin "4") (pinfunction "P$1_4") (pintype "bidirectional"))
      (node (ref "R43") (pin "2") (pinfunction "2_2") (pintype "passive"))
      (node (ref "U$10") (pin "+") (pinfunction "+_+") (pintype "passive"))
      (node (ref "U$11") (pin "+") (pinfunction "+_+") (pintype "passive"))
    )
    (net (code "36") (name "/CHARGER_CTL") (class "Default")
      (node (ref "U$12") (pin "P$1") (pinfunction "INP_P$1") (pintype "bidirectional"))
      (node (ref "U$13") (pin "8.0") (pinfunction "P8.0_8.0") (pintype "bidirectional"))
    )
    (net (code "37") (name "/CHARGER_I_MEAS") (class "Default")
      (node (ref "U$13") (pin "5.2") (pinfunction "P5.2_5.2") (pintype "bidirectional"))
      (node (ref "U$4") (pin "3") (pinfunction "VIOUT_3") (pintype "bidirectional"))
    )
    (net (code "38") (name "/ESTOP_1") (class "Default")
      (node (ref "JP3") (pin "2") (pinfunction "2_2") (pintype "passive"))
      (node (ref "R45") (pin "1") (pinfunction "1_1") (pintype "passive"))
      (node (ref "U$13") (pin "1.5") (pinfunction "P1.5_1.5") (pintype "bidirectional"))
    )
    (net (code "39") (name "/ESTOP_2") (class "Default")
      (node (ref "JP2") (pin "2") (pinfunction "2_2") (pintype "passive"))
      (node (ref "R46") (pin "1") (pinfunction "1_1") (pintype "passive"))
      (node (ref "U$13") (pin "1.6") (pinfunction "P1.6_1.6") (pintype "bidirectional"))
    )
    (net (code "40") (name "/FAN_CTL_1") (class "Default")
      (node (ref "Q12") (pin "1") (pinfunction "G_1") (pintype "passive"))
      (node (ref "U$13") (pin "2.4") (pinfunction "P2.4_2.4") (pintype "bidirectional"))
    )
    (net (code "41") (name "/FAN_CTL_2") (class "Default")
      (node (ref "Q13") (pin "1") (pinfunction "G_1") (pintype "passive"))
      (node (ref "U$13") (pin "2.5") (pinfunction "P2.5_2.5") (pintype "bidirectional"))
    )
    (net (code "42") (name "/FAN_CTL_3") (class "Default")
      (node (ref "Q14") (pin "1") (pinfunction "G_1") (pintype "passive"))
      (node (ref "U$13") (pin "2.6") (pinfunction "P2.6_2.6") (pintype "bidirectional"))
    )
    (net (code "43") (name "/FAN_CTL_4") (class "Default")
      (node (ref "Q15") (pin "1") (pinfunction "G_1") (pintype "passive"))
      (node (ref "U$13") (pin "2.7") (pinfunction "P2.7_2.7") (pintype "bidirectional"))
    )
    (net (code "44") (name "/FAN_TACH_1") (class "Default")
      (node (ref "U$13") (pin "5.0") (pinfunction "P5.0_5.0") (pintype "bidirectional"))
      (node (ref "X1") (pin "3") (pinfunction "S_3") (pintype "passive"))
    )
    (net (code "45") (name "/FAN_TACH_2") (class "Default")
      (node (ref "U$13") (pin "3.3") (pinfunction "P3.3_3.3") (pintype "bidirectional"))
      (node (ref "X2") (pin "3") (pinfunction "S_3") (pintype "passive"))
    )
    (net (code "46") (name "/FAN_TACH_3") (class "Default")
      (node (ref "U$13") (pin "3.2") (pinfunction "P3.2_3.2") (pintype "bidirectional"))
      (node (ref "X3") (pin "3") (pinfunction "S_3") (pintype "passive"))
    )
    (net (code "47") (name "/FAN_TACH_4") (class "Default")
      (node (ref "U$13") (pin "3.0") (pinfunction "P3.0_3.0") (pintype "bidirectional"))
      (node (ref "X4") (pin "3") (pinfunction "S_3") (pintype "passive"))
    )
    (net (code "48") (name "/GAUGE_ON") (class "Default")
      (node (ref "GAUGE_ON") (pin "2") (pinfunction "2_2") (pintype "passive"))
      (node (ref "IC2") (pin "P$10") (pinfunction "/G_P$10") (pintype "bidirectional"))
      (node (ref "R57") (pin "2") (pinfunction "2_2") (pintype "passive"))
      (node (ref "S2") (pin "3") (pinfunction "2_3") (pintype "passive"))
      (node (ref "U$13") (pin "6.6") (pinfunction "P6.6_6.6") (pintype "bidirectional"))
    )
    (net (code "49") (name "/LCD_DB[0]") (class "Default")
      (node (ref "JP5") (pin "7") (pinfunction "7_7") (pintype "passive"))
      (node (ref "U$13") (pin "4.0") (pinfunction "P4.0_4.0") (pintype "bidirectional"))
    )
    (net (code "50") (name "/LCD_DB[1]") (class "Default")
      (node (ref "JP5") (pin "8") (pinfunction "8_8") (pintype "passive"))
      (node (ref "U$13") (pin "4.1") (pinfunction "P4.1_4.1") (pintype "bidirectional"))
    )
    (net (code "51") (name "/LCD_DB[2]") (class "Default")
      (node (ref "JP5") (pin "9") (pinfunction "9_9") (pintype "passive"))
      (node (ref "U$13") (pin "4.2") (pinfunction "P4.2_4.2") (pintype "bidirectional"))
    )
    (net (code "52") (name "/LCD_DB[3]") (class "Default")
      (node (ref "JP5") (pin "10") (pinfunction "10_10") (pintype "passive"))
      (node (ref "U$13") (pin "4.3") (pinfunction "P4.3_4.3") (pintype "bidirectional"))
    )
    (net (code "53") (name "/LCD_DB[4]") (class "Default")
      (node (ref "JP5") (pin "11") (pinfunction "11_11") (pintype "passive"))
      (node (ref "U$13") (pin "4.4") (pinfunction "P4.4_4.4") (pintype "bidirectional"))
    )
    (net (code "54") (name "/LCD_DB[5]") (class "Default")
      (node (ref "JP5") (pin "12") (pinfunction "12_12") (pintype "passive"))
      (node (ref "U$13") (pin "4.5") (pinfunction "P4.5_4.5") (pintype "bidirectional"))
    )
    (net (code "55") (name "/LCD_DB[6]") (class "Default")
      (node (ref "JP5") (pin "13") (pinfunction "13_13") (pintype "passive"))
      (node (ref "U$13") (pin "4.6") (pinfunction "P4.6_4.6") (pintype "bidirectional"))
    )
    (net (code "56") (name "/LCD_DB[7]") (class "Default")
      (node (ref "JP5") (pin "14") (pinfunction "14_14") (pintype "passive"))
      (node (ref "U$13") (pin "4.7") (pinfunction "P4.7_4.7") (pintype "bidirectional"))
    )
    (net (code "57") (name "/LCD_EN") (class "Default")
      (node (ref "JP5") (pin "6") (pinfunction "6_6") (pintype "passive"))
      (node (ref "U$13") (pin "3.7") (pinfunction "P3.7_3.7") (pintype "bidirectional"))
    )
    (net (code "58") (name "/LCD_RS") (class "Default")
      (node (ref "JP5") (pin "4") (pinfunction "4_4") (pintype "passive"))
      (node (ref "U$13") (pin "3.5") (pinfunction "P3.5_3.5") (pintype "bidirectional"))
    )
    (net (code "59") (name "/LCD_RW") (class "Default")
      (node (ref "JP5") (pin "5") (pinfunction "5_5") (pintype "passive"))
      (node (ref "U$13") (pin "3.6") (pinfunction "P3.6_3.6") (pintype "bidirectional"))
    )
    (net (code "60") (name "/LCD_VBACK") (class "Default")
      (node (ref "JP5") (pin "3") (pinfunction "3_3") (pintype "passive"))
      (node (ref "RV1") (pin "1") (pinfunction "S_1") (pintype "passive"))
    )
    (net (code "61") (name "/LED_CLR") (class "Default")
      (node (ref "IC2") (pin "P$9") (pinfunction "/CLR_P$9") (pintype "bidirectional"))
      (node (ref "U$13") (pin "10.0") (pinfunction "P10.0_10.0") (pintype "bidirectional"))
    )
    (net (code "62") (name "/LED_RCK") (class "Default")
      (node (ref "IC2") (pin "P$12") (pinfunction "RCK_P$12") (pintype "bidirectional"))
      (node (ref "U$13") (pin "10.1") (pinfunction "P10.1_10.1") (pintype "bidirectional"))
    )
    (net (code "63") (name "/LED_SER_IN") (class "Default")
      (node (ref "IC2") (pin "P$2") (pinfunction "SER_IN_P$2") (pintype "bidirectional"))
      (node (ref "U$13") (pin "10.2") (pinfunction "P10.2_10.2") (pintype "bidirectional"))
    )
    (net (code "64") (name "/LED_SRCK") (class "Default")
      (node (ref "IC2") (pin "P$19") (pinfunction "SRCK_P$19") (pintype "bidirectional"))
      (node (ref "U$13") (pin "10.3") (pinfunction "P10.3_10.3") (pintype "bidirectional"))
    )
    (net (code "65") (name "/LOGIC_POWER") (class "Default")
      (node (ref "F1") (pin "2") (pinfunction "2_2") (pintype "bidirectional"))
      (node (ref "OKI-78SR") (pin "1") (pinfunction "VI_1") (pintype "bidirectional"))
      (node (ref "OKI-78SR1") (pin "1") (pinfunction "VI_1") (pintype "bidirectional"))
    )
    (net (code "66") (name "/N$115") (class "Default")
      (node (ref "JP5") (pin "15") (pinfunction "15_15") (pintype "passive"))
    )
    (net (code "67") (name "/N$116") (class "Default")
      (node (ref "JP5") (pin "16") (pinfunction "16_16") (pintype "passive"))
    )
    (net (code "68") (name "/PACK_GATE") (class "Default")
      (node (ref "U$13") (pin "6.0") (pinfunction "P6.0_6.0") (pintype "bidirectional"))
      (node (ref "U$8") (pin "4") (pinfunction "IN_4") (pintype "bidirectional"))
    )
    (net (code "69") (name "/PACK_I_MEAS") (class "Default")
      (node (ref "U$13") (pin "5.5") (pinfunction "P5.5_5.5") (pintype "bidirectional"))
      (node (ref "U$2") (pin "3") (pinfunction "VIOUT_3") (pintype "bidirectional"))
    )
    (net (code "70") (name "/SUPPLY_CTL") (class "Default")
      (node (ref "JP4") (pin "6") (pinfunction "6_6") (pintype "passive"))
      (node (ref "U$13") (pin "2.3") (pinfunction "P2.3_2.3") (pintype "bidirectional"))
    )
    (net (code "71") (name "/SUPPLY_DC_OK") (class "Default")
      (node (ref "JP4") (pin "1") (pinfunction "1_1") (pintype "passive"))
      (node (ref "U$13") (pin "1.7") (pinfunction "P1.7_1.7") (pintype "bidirectional"))
    )
    (net (code "72") (name "/TEMP_1") (class "Default")
      (node (ref "C11") (pin "1") (pinfunction "1_1") (pintype "passive"))
      (node (ref "R34") (pin "1") (pinfunction "1_1") (pintype "passive"))
      (node (ref "U$1") (pin "28") (pinfunction "VTEMP1_28") (pintype "bidirectional"))
    )
    (net (code "73") (name "/TEMP_2") (class "Default")
      (node (ref "C12") (pin "1") (pinfunction "1_1") (pintype "passive"))
      (node (ref "R36") (pin "1") (pinfunction "1_1") (pintype "passive"))
      (node (ref "U$1") (pin "29") (pinfunction "VTEMP2_29") (pintype "bidirectional"))
    )
    (net (code "74") (name "/V_CHECK_ARRAY") (class "Default")
      (node (ref "R41") (pin "1") (pinfunction "1_1") (pintype "passive"))
      (node (ref "R42") (pin "2") (pinfunction "2_2") (pintype "passive"))
      (node (ref "U$13") (pin "5.3") (pinfunction "P5.3_5.3") (pintype "bidirectional"))
    )
    (net (code "75") (name "/V_CHECK_CHARGER_IN") (class "Default")
      (node (ref "R43") (pin "1") (pinfunction "1_1") (pintype "passive"))
      (node (ref "R44") (pin "2") (pinfunction "2_2") (pintype "passive"))
      (node (ref "U$13") (pin "5.1") (pinfunction "P5.1_5.1") (pintype "bidirectional"))
    )
    (net (code "76") (name "/V_CHECK_OUT") (class "Default")
      (node (ref "R38") (pin "2") (pinfunction "2_2") (pintype "passive"))
      (node (ref "R39") (pin "1") (pinfunction "1_1") (pintype "passive"))
      (node (ref "U$13") (pin "5.4") (pinfunction "P5.4_5.4") (pintype "bidirectional"))
    )
    (net (code "77") (name "/WIZNET_DATA_INT") (class "Default")
      (node (ref "U$13") (pin "6.1") (pinfunction "P6.1_6.1") (pintype "bidirectional"))
      (node (ref "U1") (pin "28") (pinfunction "/INT_28") (pintype "bidirectional"))
    )
    (net (code "78") (name "/WIZNET_MISO") (class "Default")
      (node (ref "U$13") (pin "9.6") (pinfunction "P9.6_9.6") (pintype "bidirectional"))
      (node (ref "U1") (pin "2") (pinfunction "MISO_2") (pintype "bidirectional"))
    )
    (net (code "79") (name "/WIZNET_MOSI") (class "Default")
      (node (ref "U$13") (pin "9.7") (pinfunction "P9.7_9.7") (pintype "bidirectional"))
      (node (ref "U1") (pin "1") (pinfunction "MOSI_1") (pintype "bidirectional"))
    )
    (net (code "80") (name "/WIZNET_RESET") (class "Default")
      (node (ref "U$13") (pin "9.0") (pinfunction "P9.0_9.0") (pintype "bidirectional"))
      (node (ref "U1") (pin "22") (pinfunction "/RESET_22") (pintype "bidirectional"))
    )
    (net (code "81") (name "/WIZNET_SCLK") (class "Default")
      (node (ref "U$13") (pin "9.5") (pinfunction "P9.5_9.5") (pintype "bidirectional"))
      (node (ref "U1") (pin "23") (pinfunction "SCLK_23") (pintype "bidirectional"))
    )
    (net (code "82") (name "/WIZNET_SS") (class "Default")
      (node (ref "U$13") (pin "9.4") (pinfunction "P9.4_9.4") (pintype "bidirectional"))
      (node (ref "U1") (pin "24") (pinfunction "/SCS_24") (pintype "bidirectional"))
    )
    (net (code "83") (name "5V") (class "Default")
      (node (ref "BUZZER_1") (pin "+") (pinfunction "1_+") (pintype "passive"))
      (node (ref "BUZZER_2") (pin "-") (pinfunction "2_-") (pintype "passive"))
      (node (ref "C18") (pin "1") (pinfunction "1_1") (pintype "passive"))
      (node (ref "C21") (pin "1") (pinfunction "1_1") (pintype "passive"))
      (node (ref "IC2") (pin "P$1") (pinfunction "VCC_P$1") (pintype "bidirectional"))
      (node (ref "JP5") (pin "2") (pinfunction "2_2") (pintype "passive"))
      (node (ref "L3") (pin "2") (pinfunction "2_2") (pintype "passive"))
      (node (ref "R45") (pin "2") (pinfunction "2_2") (pintype "passive"))
      (node (ref "R46") (pin "2") (pinfunction "2_2") (pintype "passive"))
      (node (ref "R47") (pin "2") (pinfunction "2_2") (pintype "passive"))
      (node (ref "R48") (pin "2") (pinfunction "2_2") (pintype "passive"))
      (node (ref "R49") (pin "2") (pinfunction "2_2") (pintype "passive"))
      (node (ref "R50") (pin "2") (pinfunction "2_2") (pintype "passive"))
      (node (ref "R51") (pin "2") (pinfunction "2_2") (pintype "passive"))
      (node (ref "R52") (pin "2") (pinfunction "2_2") (pintype "passive"))
      (node (ref "R53") (pin "2") (pinfunction "2_2") (pintype "passive"))
      (node (ref "R54") (pin "2") (pinfunction "2_2") (pintype "passive"))
      (node (ref "R55") (pin "2") (pinfunction "2_2") (pintype "passive"))
      (node (ref "R56") (pin "2") (pinfunction "2_2") (pintype "passive"))
      (node (ref "R57") (pin "1") (pinfunction "1_1") (pintype "passive"))
      (node (ref "R58") (pin "1") (pinfunction "1_1") (pintype "passive"))
      (node (ref "R59") (pin "1") (pinfunction "1_1") (pintype "passive"))
      (node (ref "R60") (pin "1") (pinfunction "1_1") (pintype "passive"))
      (node (ref "R61") (pin "1") (pinfunction "1_1") (pintype "passive"))
      (node (ref "R62") (pin "1") (pinfunction "1_1") (pintype "passive"))
      (node (ref "R63") (pin "1") (pinfunction "1_1") (pintype "passive"))
      (node (ref "R64") (pin "1") (pinfunction "1_1") (pintype "passive"))
      (node (ref "R65") (pin "1") (pinfunction "1_1") (pintype "passive"))
      (node (ref "R66") (pin "1") (pinfunction "1_1") (pintype "passive"))
      (node (ref "R67") (pin "1") (pinfunction "1_1") (pintype "passive"))
      (node (ref "RV1") (pin "3") (pinfunction "A_3") (pintype "passive"))
      (node (ref "U$13") (pin "5V_1") (pinfunction "5V_1_5V_1") (pintype "bidirectional"))
      (node (ref "U$13") (pin "5V_2") (pinfunction "5V_2_5V_2") (pintype "bidirectional"))
      (node (ref "U$13") (pin "5V_3") (pinfunction "5V_3_5V_3") (pintype "bidirectional"))
      (node (ref "U$13") (pin "5V_4") (pinfunction "5V_4_5V_4") (pintype "bidirectional"))
    )
    (net (code "84") (name "GND") (class "Default")
      (node (ref "C1") (pin "2") (pinfunction "2_2") (pintype "passive"))
      (node (ref "C10") (pin "2") (pinfunction "2_2") (pintype "passive"))
      (node (ref "C11") (pin "2") (pinfunction "2_2") (pintype "passive"))
      (node (ref "C12") (pin "2") (pinfunction "2_2") (pintype "passive"))
      (node (ref "C13") (pin "2") (pinfunction "2_2") (pintype "passive"))
      (node (ref "C14") (pin "2") (pinfunction "2_2") (pintype "passive"))
      (node (ref "C16") (pin "2") (pinfunction "2_2") (pintype "passive"))
      (node (ref "C17") (pin "2") (pinfunction "2_2") (pintype "passive"))
      (node (ref "C18") (pin "2") (pinfunction "2_2") (pintype "passive"))
      (node (ref "C19") (pin "2") (pinfunction "2_2") (pintype "passive"))
      (node (ref "C2") (pin "2") (pinfunction "2_2") (pintype "passive"))
      (node (ref "C20") (pin "2") (pinfunction "2_2") (pintype "passive"))
      (node (ref "C21") (pin "2") (pinfunction "2_2") (pintype "passive"))
      (node (ref "C3") (pin "2") (pinfunction "2_2") (pintype "passive"))
      (node (ref "C4") (pin "2") (pinfunction "2_2") (pintype "passive"))
      (node (ref "C5") (pin "2") (pinfunction "2_2") (pintype "passive"))
      (node (ref "C6") (pin "2") (pinfunction "2_2") (pintype "passive"))
      (node (ref "C7") (pin "2") (pinfunction "2_2") (pintype "passive"))
      (node (ref "C8") (pin "2") (pinfunction "2_2") (pintype "passive"))
      (node (ref "C9") (pin "2") (pinfunction "2_2") (pintype "passive"))
      (node (ref "CELL-IN") (pin "9") (pinfunction "S_9") (pintype "passive"))
      (node (ref "CELL-MEAS") (pin "9") (pinfunction "S_9") (pintype "passive"))
      (node (ref "CHARGER-") (pin "P$1") (pinfunction "P$1_P$1") (pintype "bidirectional"))
      (node (ref "D1") (pin "A") (pinfunction "A_A") (pintype "passive"))
      (node (ref "D17") (pin "A") (pinfunction "A_A") (pintype "passive"))
      (node (ref "D18") (pin "A") (pinfunction "A_A") (pintype "passive"))
      (node (ref "D19") (pin "A") (pinfunction "A_A") (pintype "passive"))
      (node (ref "D2") (pin "C") (pinfunction "C_C") (pintype "passive"))
      (node (ref "GAUGE_ON") (pin "1") (pinfunction "1_1") (pintype "passive"))
      (node (ref "IC1") (pin "4") (pinfunction "V-_4") (pintype "power_in"))
      (node (ref "IC2") (pin "P$20") (pinfunction "GND_P$20") (pintype "bidirectional"))
      (node (ref "JP2") (pin "1") (pinfunction "1_1") (pintype "passive"))
      (node (ref "JP3") (pin "1") (pinfunction "1_1") (pintype "passive"))
      (node (ref "JP4") (pin "2") (pinfunction "2_2") (pintype "passive"))
      (node (ref "JP4") (pin "3") (pinfunction "3_3") (pintype "passive"))
      (node (ref "JP4") (pin "5") (pinfunction "5_5") (pintype "passive"))
      (node (ref "JP5") (pin "1") (pinfunction "1_1") (pintype "passive"))
      (node (ref "OKI-78SR") (pin "2") (pinfunction "GND_2") (pintype "bidirectional"))
      (node (ref "OKI-78SR1") (pin "2") (pinfunction "GND_2") (pintype "bidirectional"))
      (node (ref "Q10") (pin "2") (pinfunction "S_2") (pintype "passive"))
      (node (ref "Q11") (pin "2") (pinfunction "S_2") (pintype "passive"))
      (node (ref "Q12") (pin "2") (pinfunction "S_2") (pintype "passive"))
      (node (ref "Q13") (pin "2") (pinfunction "S_2") (pintype "passive"))
      (node (ref "Q14") (pin "2") (pinfunction "S_2") (pintype "passive"))
      (node (ref "Q15") (pin "2") (pinfunction "S_2") (pintype "passive"))
      (node (ref "R2") (pin "P$2") (pinfunction "2_P$2") (pintype "passive"))
      (node (ref "R39") (pin "2") (pinfunction "2_2") (pintype "passive"))
      (node (ref "R40") (pin "2") (pinfunction "2_2") (pintype "passive"))
      (node (ref "R42") (pin "1") (pinfunction "1_1") (pintype "passive"))
      (node (ref "R44") (pin "1") (pinfunction "1_1") (pintype "passive"))
      (node (ref "RV1") (pin "2") (pinfunction "E_2") (pintype "passive"))
      (node (ref "S1") (pin "3") (pinfunction "S_3") (pintype "passive"))
      (node (ref "S2") (pin "1") (pinfunction "1_1") (pintype "passive"))
      (node (ref "THERM_1") (pin "2") (pinfunction "S_2") (pintype "passive"))
      (node (ref "THERM_2") (pin "2") (pinfunction "S_2") (pintype "passive"))
      (node (ref "U$1") (pin "26") (pinfunction "V-_26") (pintype "bidirectional"))
      (node (ref "U$1") (pin "32") (pinfunction "TOS_32") (pintype "bidirectional"))
      (node (ref "U$1") (pin "35") (pinfunction "GPIO1_35") (pintype "bidirectional"))
      (node (ref "U$1") (pin "36") (pinfunction "GPIO2_36") (pintype "bidirectional"))
      (node (ref "U$1") (pin "37") (pinfunction "A0_37") (pintype "bidirectional"))
      (node (ref "U$1") (pin "38") (pinfunction "A1_38") (pintype "bidirectional"))
      (node (ref "U$1") (pin "39") (pinfunction "A2_39") (pintype "bidirectional"))
      (node (ref "U$1") (pin "40") (pinfunction "A3_40") (pintype "bidirectional"))
      (node (ref "U$10") (pin "GND") (pinfunction "-_GND") (pintype "passive"))
      (node (ref "U$11") (pin "GND") (pinfunction "-_GND") (pintype "passive"))
      (node (ref "U$12") (pin "P$2") (pinfunction "GND_P$2") (pintype "bidirectional"))
      (node (ref "U$12") (pin "P$4") (pinfunction "GND_P$4") (pintype "bidirectional"))
      (node (ref "U$12") (pin "P$9") (pinfunction "GND_P$9") (pintype "bidirectional"))
      (node (ref "U$13") (pin "GND_1") (pinfunction "GND1_GND_1") (pintype "bidirectional"))
      (node (ref "U$13") (pin "GND_2") (pinfunction "GND2_GND_2") (pintype "bidirectional"))
      (node (ref "U$13") (pin "GND_3") (pinfunction "GND3_GND_3") (pintype "bidirectional"))
      (node (ref "U$13") (pin "GND_4") (pinfunction "GND4_GND_4") (pintype "bidirectional"))
      (node (ref "U$13") (pin "GND_5") (pinfunction "GND5_GND_5") (pintype "bidirectional"))
      (node (ref "U$13") (pin "GND_6") (pinfunction "GND6_GND_6") (pintype "bidirectional"))
      (node (ref "U$13") (pin "GND_7") (pinfunction "GND7_GND_7") (pintype "bidirectional"))
      (node (ref "U$13") (pin "GND_8") (pinfunction "GND8_GND_8") (pintype "bidirectional"))
      (node (ref "U$2") (pin "2") (pinfunction "GND_2") (pintype "bidirectional"))
      (node (ref "U$3") (pin "GND") (pinfunction "-_GND") (pintype "passive"))
      (node (ref "U$4") (pin "2") (pinfunction "GND_2") (pintype "bidirectional"))
      (node (ref "U$6") (pin "GND") (pinfunction "-_GND") (pintype "passive"))
      (node (ref "U$7") (pin "GND") (pinfunction "-_GND") (pintype "passive"))
      (node (ref "U$8") (pin "1") (pinfunction "GND_1") (pintype "bidirectional"))
      (node (ref "U$9") (pin "P$1") (pinfunction "A_P$1") (pintype "passive"))
      (node (ref "U$9") (pin "P$3") (pinfunction "A_P$3") (pintype "passive"))
      (node (ref "U1") (pin "11") (pinfunction "GND_11") (pintype "bidirectional"))
      (node (ref "U1") (pin "29") (pinfunction "GND_29") (pintype "bidirectional"))
      (node (ref "U1") (pin "30") (pinfunction "GND_30") (pintype "bidirectional"))
      (node (ref "U1") (pin "39") (pinfunction "GND_39") (pintype "bidirectional"))
      (node (ref "U1") (pin "40") (pinfunction "GND_40") (pintype "bidirectional"))
      (node (ref "V_OUT1") (pin "P$1") (pinfunction "P$1_P$1") (pintype "bidirectional"))
    )
    (net (code "85") (name "Net-(BUZZER_1-2)") (class "Default")
      (node (ref "BUZZER_1") (pin "-") (pinfunction "2_-") (pintype "passive"))
      (node (ref "Q11") (pin "3") (pinfunction "D_3") (pintype "passive"))
    )
    (net (code "86") (name "Net-(BUZZER_2-1)") (class "Default")
      (node (ref "BUZZER_2") (pin "+") (pinfunction "1_+") (pintype "passive"))
      (node (ref "Q10") (pin "3") (pinfunction "D_3") (pintype "passive"))
    )
    (net (code "87") (name "Net-(D2-PadA)") (class "Default")
      (node (ref "D2") (pin "A") (pinfunction "A_A") (pintype "passive"))
      (node (ref "R3") (pin "2") (pinfunction "2_2") (pintype "passive"))
    )
    (net (code "88") (name "Net-(D4-PadA)") (class "Default")
      (node (ref "D4") (pin "A") (pinfunction "A_A") (pintype "passive"))
      (node (ref "R7") (pin "2") (pinfunction "2_2") (pintype "passive"))
    )
    (net (code "89") (name "Net-(D6-PadA)") (class "Default")
      (node (ref "D6") (pin "A") (pinfunction "A_A") (pintype "passive"))
      (node (ref "R11") (pin "2") (pinfunction "2_2") (pintype "passive"))
    )
    (net (code "90") (name "Net-(D8-PadA)") (class "Default")
      (node (ref "D8") (pin "A") (pinfunction "A_A") (pintype "passive"))
      (node (ref "R15") (pin "2") (pinfunction "2_2") (pintype "passive"))
    )
    (net (code "91") (name "Net-(D10-PadA)") (class "Default")
      (node (ref "D10") (pin "A") (pinfunction "A_A") (pintype "passive"))
      (node (ref "R19") (pin "2") (pinfunction "2_2") (pintype "passive"))
    )
    (net (code "92") (name "Net-(D12-PadA)") (class "Default")
      (node (ref "D12") (pin "A") (pinfunction "A_A") (pintype "passive"))
      (node (ref "R23") (pin "2") (pinfunction "2_2") (pintype "passive"))
    )
    (net (code "93") (name "Net-(D14-PadA)") (class "Default")
      (node (ref "D14") (pin "A") (pinfunction "A_A") (pintype "passive"))
      (node (ref "R27") (pin "2") (pinfunction "2_2") (pintype "passive"))
    )
    (net (code "94") (name "Net-(D16-PadA)") (class "Default")
      (node (ref "D16") (pin "A") (pinfunction "A_A") (pintype "passive"))
      (node (ref "R31") (pin "2") (pinfunction "2_2") (pintype "passive"))
    )
    (net (code "95") (name "Net-(D17-PadC)") (class "Default")
      (node (ref "D17") (pin "C") (pinfunction "C_C") (pintype "passive"))
      (node (ref "D18") (pin "C") (pinfunction "C_C") (pintype "passive"))
      (node (ref "D19") (pin "C") (pinfunction "C_C") (pintype "passive"))
      (node (ref "L1") (pin "2") (pinfunction "2_2") (pintype "passive"))
      (node (ref "R37") (pin "2") (pinfunction "2_2") (pintype "passive"))
    )
    (net (code "96") (name "Net-(D20-C)") (class "Default")
      (node (ref "C15") (pin "1") (pinfunction "1_1") (pintype "passive"))
      (node (ref "D20") (pin "3") (pinfunction "C_3") (pintype "passive"))
      (node (ref "U$12") (pin "P$6") (pinfunction "BOOST_P$6") (pintype "bidirectional"))
    )
    (net (code "97") (name "Net-(GAGUE_S-Pad1)") (class "Default")
      (node (ref "GAGUE_S") (pin "1") (pinfunction "1_1") (pintype "passive"))
      (node (ref "R58") (pin "2") (pinfunction "2_2") (pintype "passive"))
    )
    (net (code "98") (name "Net-(GAGUE_S-Pad2)") (class "Default")
      (node (ref "GAGUE_S") (pin "2") (pinfunction "2_2") (pintype "passive"))
      (node (ref "R59") (pin "2") (pinfunction "2_2") (pintype "passive"))
    )
    (net (code "99") (name "Net-(GAGUE_S-Pad3)") (class "Default")
      (node (ref "GAGUE_S") (pin "3") (pinfunction "3_3") (pintype "passive"))
      (node (ref "R60") (pin "2") (pinfunction "2_2") (pintype "passive"))
    )
    (net (code "100") (name "Net-(GAGUE_S-Pad4)") (class "Default")
      (node (ref "GAGUE_S") (pin "4") (pinfunction "4_4") (pintype "passive"))
      (node (ref "R61") (pin "2") (pinfunction "2_2") (pintype "passive"))
    )
    (net (code "101") (name "Net-(GAGUE_S-Pad5)") (class "Default")
      (node (ref "GAGUE_S") (pin "5") (pinfunction "5_5") (pintype "passive"))
      (node (ref "R62") (pin "2") (pinfunction "2_2") (pintype "passive"))
    )
    (net (code "102") (name "Net-(GAGUE_S-Pad6)") (class "Default")
      (node (ref "GAGUE_S") (pin "6") (pinfunction "6_6") (pintype "passive"))
      (node (ref "R63") (pin "2") (pinfunction "2_2") (pintype "passive"))
    )
    (net (code "103") (name "Net-(GAGUE_S-Pad7)") (class "Default")
      (node (ref "GAGUE_S") (pin "7") (pinfunction "7_7") (pintype "passive"))
      (node (ref "R64") (pin "2") (pinfunction "2_2") (pintype "passive"))
    )
    (net (code "104") (name "Net-(GAGUE_S-Pad8)") (class "Default")
      (node (ref "GAGUE_S") (pin "8") (pinfunction "8_8") (pintype "passive"))
      (node (ref "R65") (pin "2") (pinfunction "2_2") (pintype "passive"))
    )
    (net (code "105") (name "Net-(GAGUE_S-Pad9)") (class "Default")
      (node (ref "GAGUE_S") (pin "9") (pinfunction "9_9") (pintype "passive"))
      (node (ref "R66") (pin "2") (pinfunction "2_2") (pintype "passive"))
    )
    (net (code "106") (name "Net-(GAGUE_S-Pad10)") (class "Default")
      (node (ref "GAGUE_S") (pin "10") (pinfunction "10_10") (pintype "passive"))
      (node (ref "R67") (pin "2") (pinfunction "2_2") (pintype "passive"))
    )
    (net (code "107") (name "Net-(IC1A--IN)") (class "Default")
      (node (ref "IC1") (pin "1") (pinfunction "OUT_1") (pintype "output"))
      (node (ref "IC1") (pin "2") (pinfunction "-IN_2") (pintype "input"))
      (node (ref "R33") (pin "1") (pinfunction "1_1") (pintype "passive"))
    )
    (net (code "108") (name "Net-(IC1B--IN)") (class "Default")
      (node (ref "IC1") (pin "6") (pinfunction "-IN_6") (pintype "input"))
      (node (ref "IC1") (pin "7") (pinfunction "OUT_7") (pintype "output"))
      (node (ref "R35") (pin "1") (pinfunction "1_1") (pintype "passive"))
    )
    (net (code "109") (name "Net-(IC2-DRAIN0)") (class "Default")
      (node (ref "IC2") (pin "P$3") (pinfunction "DRAIN0_P$3") (pintype "bidirectional"))
      (node (ref "JP1") (pin "10") (pinfunction "10_10") (pintype "passive"))
      (node (ref "LED2") (pin "P$20") (pinfunction "20_P$20") (pintype "bidirectional"))
    )
    (net (code "110") (name "Net-(IC2-DRAIN1)") (class "Default")
      (node (ref "IC2") (pin "P$4") (pinfunction "DRAIN1_P$4") (pintype "bidirectional"))
      (node (ref "JP1") (pin "9") (pinfunction "9_9") (pintype "passive"))
      (node (ref "LED2") (pin "P$19") (pinfunction "19_P$19") (pintype "bidirectional"))
    )
    (net (code "111") (name "Net-(IC2-DRAIN2)") (class "Default")
      (node (ref "IC2") (pin "P$5") (pinfunction "DRAIN2_P$5") (pintype "bidirectional"))
      (node (ref "JP1") (pin "8") (pinfunction "8_8") (pintype "passive"))
      (node (ref "LED2") (pin "P$18") (pinfunction "18_P$18") (pintype "bidirectional"))
    )
    (net (code "112") (name "Net-(IC2-DRAIN3)") (class "Default")
      (node (ref "IC2") (pin "P$6") (pinfunction "DRAIN3_P$6") (pintype "bidirectional"))
      (node (ref "JP1") (pin "7") (pinfunction "7_7") (pintype "passive"))
      (node (ref "LED2") (pin "P$17") (pinfunction "17_P$17") (pintype "bidirectional"))
    )
    (net (code "113") (name "Net-(IC2-DRAIN4)") (class "Default")
      (node (ref "IC2") (pin "P$7") (pinfunction "DRAIN4_P$7") (pintype "bidirectional"))
      (node (ref "JP1") (pin "6") (pinfunction "6_6") (pintype "passive"))
      (node (ref "LED2") (pin "P$16") (pinfunction "16_P$16") (pintype "bidirectional"))
    )
    (net (code "114") (name "Net-(IC2-DRAIN5)") (class "Default")
      (node (ref "IC2") (pin "P$8") (pinfunction "DRAIN5_P$8") (pintype "bidirectional"))
      (node (ref "JP1") (pin "5") (pinfunction "5_5") (pintype "passive"))
      (node (ref "LED2") (pin "P$15") (pinfunction "15_P$15") (pintype "bidirectional"))
    )
    (net (code "115") (name "Net-(IC2-DRAIN6)") (class "Default")
      (node (ref "IC2") (pin "P$13") (pinfunction "DRAIN6_P$13") (pintype "bidirectional"))
      (node (ref "JP1") (pin "4") (pinfunction "4_4") (pintype "passive"))
      (node (ref "LED2") (pin "P$14") (pinfunction "14_P$14") (pintype "bidirectional"))
    )
    (net (code "116") (name "Net-(IC2-DRAIN7)") (class "Default")
      (node (ref "IC2") (pin "P$14") (pinfunction "DRAIN7_P$14") (pintype "bidirectional"))
      (node (ref "JP1") (pin "3") (pinfunction "3_3") (pintype "passive"))
      (node (ref "LED2") (pin "P$13") (pinfunction "13_P$13") (pintype "bidirectional"))
    )
    (net (code "117") (name "Net-(IC2-DRAIN8)") (class "Default")
      (node (ref "IC2") (pin "P$15") (pinfunction "DRAIN8_P$15") (pintype "bidirectional"))
      (node (ref "JP1") (pin "2") (pinfunction "2_2") (pintype "passive"))
      (node (ref "LED2") (pin "P$12") (pinfunction "12_P$12") (pintype "bidirectional"))
    )
    (net (code "118") (name "Net-(IC2-DRAIN9)") (class "Default")
      (node (ref "IC2") (pin "P$16") (pinfunction "DRAIN9_P$16") (pintype "bidirectional"))
      (node (ref "JP1") (pin "1") (pinfunction "1_1") (pintype "passive"))
      (node (ref "LED2") (pin "P$11") (pinfunction "11_P$11") (pintype "bidirectional"))
    )
    (net (code "119") (name "Net-(IRLS3034-7P-DRAIN)") (class "Default")
      (node (ref "C14") (pin "1") (pinfunction "1_1") (pintype "passive"))
      (node (ref "IRLS3034-7P") (pin "PAD") (pinfunction "DRAIN_PAD") (pintype "bidirectional"))
      (node (ref "IRLS3034-7P.2") (pin "PAD") (pinfunction "DRAIN_PAD") (pintype "bidirectional"))
      (node (ref "R41") (pin "2") (pinfunction "2_2") (pintype "passive"))
      (node (ref "S1") (pin "1") (pinfunction "O_1") (pintype "passive"))
      (node (ref "U$2") (pin "5_1") (pinfunction "IP-_5_1") (pintype "bidirectional"))
      (node (ref "U$2") (pin "5_10") (pinfunction "IP-_5_10") (pintype "bidirectional"))
      (node (ref "U$2") (pin "5_11") (pinfunction "IP-_5_11") (pintype "bidirectional"))
      (node (ref "U$2") (pin "5_12") (pinfunction "IP-_5_12") (pintype "bidirectional"))
      (node (ref "U$2") (pin "5_13") (pinfunction "IP-_5_13") (pintype "bidirectional"))
      (node (ref "U$2") (pin "5_14") (pinfunction "IP-_5_14") (pintype "bidirectional"))
      (node (ref "U$2") (pin "5_15") (pinfunction "IP-_5_15") (pintype "bidirectional"))
      (node (ref "U$2") (pin "5_16") (pinfunction "IP-_5_16") (pintype "bidirectional"))
      (node (ref "U$2") (pin "5_2") (pinfunction "IP-_5_2") (pintype "bidirectional"))
      (node (ref "U$2") (pin "5_3") (pinfunction "IP-_5_3") (pintype "bidirectional"))
      (node (ref "U$2") (pin "5_4") (pinfunction "IP-_5_4") (pintype "bidirectional"))
      (node (ref "U$2") (pin "5_5") (pinfunction "IP-_5_5") (pintype "bidirectional"))
      (node (ref "U$2") (pin "5_6") (pinfunction "IP-_5_6") (pintype "bidirectional"))
      (node (ref "U$2") (pin "5_7") (pinfunction "IP-_5_7") (pintype "bidirectional"))
      (node (ref "U$2") (pin "5_8") (pinfunction "IP-_5_8") (pintype "bidirectional"))
      (node (ref "U$2") (pin "5_9") (pinfunction "IP-_5_9") (pintype "bidirectional"))
      (node (ref "U$2") (pin "5_B") (pinfunction "IP-_5_B") (pintype "bidirectional"))
      (node (ref "U$2") (pin "5_T") (pinfunction "IP-_5_T") (pintype "bidirectional"))
      (node (ref "U$4") (pin "4_1") (pinfunction "IP+_4_1") (pintype "bidirectional"))
      (node (ref "U$4") (pin "4_10") (pinfunction "IP+_4_10") (pintype "bidirectional"))
      (node (ref "U$4") (pin "4_11") (pinfunction "IP+_4_11") (pintype "bidirectional"))
      (node (ref "U$4") (pin "4_12") (pinfunction "IP+_4_12") (pintype "bidirectional"))
      (node (ref "U$4") (pin "4_13") (pinfunction "IP+_4_13") (pintype "bidirectional"))
      (node (ref "U$4") (pin "4_14") (pinfunction "IP+_4_14") (pintype "bidirectional"))
      (node (ref "U$4") (pin "4_15") (pinfunction "IP+_4_15") (pintype "bidirectional"))
      (node (ref "U$4") (pin "4_16") (pinfunction "IP+_4_16") (pintype "bidirectional"))
      (node (ref "U$4") (pin "4_2") (pinfunction "IP+_4_2") (pintype "bidirectional"))
      (node (ref "U$4") (pin "4_3") (pinfunction "IP+_4_3") (pintype "bidirectional"))
      (node (ref "U$4") (pin "4_4") (pinfunction "IP+_4_4") (pintype "bidirectional"))
      (node (ref "U$4") (pin "4_5") (pinfunction "IP+_4_5") (pintype "bidirectional"))
      (node (ref "U$4") (pin "4_6") (pinfunction "IP+_4_6") (pintype "bidirectional"))
      (node (ref "U$4") (pin "4_7") (pinfunction "IP+_4_7") (pintype "bidirectional"))
      (node (ref "U$4") (pin "4_8") (pinfunction "IP+_4_8") (pintype "bidirectional"))
      (node (ref "U$4") (pin "4_9") (pinfunction "IP+_4_9") (pintype "bidirectional"))
      (node (ref "U$4") (pin "4_B") (pinfunction "IP+_4_B") (pintype "bidirectional"))
      (node (ref "U$4") (pin "4_T") (pinfunction "IP+_4_T") (pintype "bidirectional"))
      (node (ref "U$8") (pin "6") (pinfunction "SENSE_6") (pintype "bidirectional"))
      (node (ref "U$8") (pin "8") (pinfunction "V+_8") (pintype "bidirectional"))
    )
    (net (code "120") (name "Net-(IRLS3034-7P-GATE)") (class "Default")
      (node (ref "IRLS3034-7P") (pin "1") (pinfunction "GATE_1") (pintype "bidirectional"))
      (node (ref "IRLS3034-7P.2") (pin "1") (pinfunction "GATE_1") (pintype "bidirectional"))
      (node (ref "U$8") (pin "5") (pinfunction "GATE_5") (pintype "bidirectional"))
    )
    (net (code "121") (name "Net-(IRLS3034-7P-SOURCE-Pad2)") (class "Default")
      (node (ref "IRLS3034-7P") (pin "2") (pinfunction "SOURCE_2") (pintype "bidirectional"))
      (node (ref "IRLS3034-7P") (pin "3") (pinfunction "SOURCE_3") (pintype "bidirectional"))
      (node (ref "IRLS3034-7P") (pin "4") (pinfunction "SOURCE_4") (pintype "bidirectional"))
      (node (ref "IRLS3034-7P") (pin "5") (pinfunction "SOURCE_5") (pintype "bidirectional"))
      (node (ref "IRLS3034-7P") (pin "6") (pinfunction "SOURCE_6") (pintype "bidirectional"))
      (node (ref "IRLS3034-7P.2") (pin "2") (pinfunction "SOURCE_2") (pintype "bidirectional"))
      (node (ref "IRLS3034-7P.2") (pin "3") (pinfunction "SOURCE_3") (pintype "bidirectional"))
      (node (ref "IRLS3034-7P.2") (pin "4") (pinfunction "SOURCE_4") (pintype "bidirectional"))
      (node (ref "IRLS3034-7P.2") (pin "5") (pinfunction "SOURCE_5") (pintype "bidirectional"))
      (node (ref "IRLS3034-7P.2") (pin "6") (pinfunction "SOURCE_6") (pintype "bidirectional"))
      (node (ref "LED1") (pin "A") (pinfunction "A_A") (pintype "passive"))
      (node (ref "R38") (pin "1") (pinfunction "1_1") (pintype "passive"))
      (node (ref "V_OUT") (pin "P$1") (pinfunction "P$1_P$1") (pintype "bidirectional"))
    )
    (net (code "122") (name "Net-(LED1-PadC)") (class "Default")
      (node (ref "LED1") (pin "C") (pinfunction "C_C") (pintype "passive"))
      (node (ref "R40") (pin "1") (pinfunction "1_1") (pintype "passive"))
    )
    (net (code "123") (name "Net-(LED2-1)") (class "Default")
      (node (ref "LED2") (pin "P$1") (pinfunction "1_P$1") (pintype "bidirectional"))
      (node (ref "R47") (pin "1") (pinfunction "1_1") (pintype "passive"))
    )
    (net (code "124") (name "Net-(LED2-2)") (class "Default")
      (node (ref "LED2") (pin "P$2") (pinfunction "2_P$2") (pintype "bidirectional"))
      (node (ref "R48") (pin "1") (pinfunction "1_1") (pintype "passive"))
    )
    (net (code "125") (name "Net-(LED2-3)") (class "Default")
      (node (ref "LED2") (pin "P$3") (pinfunction "3_P$3") (pintype "bidirectional"))
      (node (ref "R49") (pin "1") (pinfunction "1_1") (pintype "passive"))
    )
    (net (code "126") (name "Net-(LED2-4)") (class "Default")
      (node (ref "LED2") (pin "P$4") (pinfunction "4_P$4") (pintype "bidirectional"))
      (node (ref "R50") (pin "1") (pinfunction "1_1") (pintype "passive"))
    )
    (net (code "127") (name "Net-(LED2-5)") (class "Default")
      (node (ref "LED2") (pin "P$5") (pinfunction "5_P$5") (pintype "bidirectional"))
      (node (ref "R51") (pin "1") (pinfunction "1_1") (pintype "passive"))
    )
    (net (code "128") (name "Net-(LED2-6)") (class "Default")
      (node (ref "LED2") (pin "P$6") (pinfunction "6_P$6") (pintype "bidirectional"))
      (node (ref "R52") (pin "1") (pinfunction "1_1") (pintype "passive"))
    )
    (net (code "129") (name "Net-(LED2-7)") (class "Default")
      (node (ref "LED2") (pin "P$7") (pinfunction "7_P$7") (pintype "bidirectional"))
      (node (ref "R53") (pin "1") (pinfunction "1_1") (pintype "passive"))
    )
    (net (code "130") (name "Net-(LED2-8)") (class "Default")
      (node (ref "LED2") (pin "P$8") (pinfunction "8_P$8") (pintype "bidirectional"))
      (node (ref "R54") (pin "1") (pinfunction "1_1") (pintype "passive"))
    )
    (net (code "131") (name "Net-(LED2-9)") (class "Default")
      (node (ref "LED2") (pin "P$9") (pinfunction "9_P$9") (pintype "bidirectional"))
      (node (ref "R55") (pin "1") (pinfunction "1_1") (pintype "passive"))
    )
    (net (code "132") (name "Net-(LED2-10)") (class "Default")
      (node (ref "LED2") (pin "P$10") (pinfunction "10_P$10") (pintype "bidirectional"))
      (node (ref "R56") (pin "1") (pinfunction "1_1") (pintype "passive"))
    )
    (net (code "133") (name "Net-(OKI-78SR-VO)") (class "Default")
      (node (ref "C17") (pin "1") (pinfunction "1_1") (pintype "passive"))
      (node (ref "L3") (pin "1") (pinfunction "1_1") (pintype "passive"))
      (node (ref "OKI-78SR") (pin "3") (pinfunction "VO_3") (pintype "bidirectional"))
    )
    (net (code "134") (name "Net-(OKI-78SR1-VO)") (class "Default")
      (node (ref "C19") (pin "1") (pinfunction "1_1") (pintype "passive"))
      (node (ref "L2") (pin "1") (pinfunction "1_1") (pintype "passive"))
      (node (ref "OKI-78SR1") (pin "3") (pinfunction "VO_3") (pintype "bidirectional"))
    )
    (net (code "135") (name "Net-(Q1-D)") (class "Default")
      (node (ref "Q1") (pin "3") (pinfunction "D_3") (pintype "passive"))
      (node (ref "R2") (pin "P$1") (pinfunction "1_P$1") (pintype "passive"))
      (node (ref "R3") (pin "1") (pinfunction "1_1") (pintype "passive"))
    )
    (net (code "136") (name "Net-(Q1-G)") (class "Default")
      (node (ref "Q1") (pin "1") (pinfunction "G_1") (pintype "passive"))
      (node (ref "R4") (pin "2") (pinfunction "2_2") (pintype "passive"))
    )
    (net (code "137") (name "Net-(Q2-D)") (class "Default")
      (node (ref "Q2") (pin "3") (pinfunction "D_3") (pintype "passive"))
      (node (ref "R6") (pin "P$1") (pinfunction "1_P$1") (pintype "passive"))
      (node (ref "R7") (pin "1") (pinfunction "1_1") (pintype "passive"))
    )
    (net (code "138") (name "Net-(Q2-G)") (class "Default")
      (node (ref "Q2") (pin "1") (pinfunction "G_1") (pintype "passive"))
      (node (ref "R8") (pin "2") (pinfunction "2_2") (pintype "passive"))
    )
    (net (code "139") (name "Net-(Q3-D)") (class "Default")
      (node (ref "Q3") (pin "3") (pinfunction "D_3") (pintype "passive"))
      (node (ref "R10") (pin "P$1") (pinfunction "1_P$1") (pintype "passive"))
      (node (ref "R11") (pin "1") (pinfunction "1_1") (pintype "passive"))
    )
    (net (code "140") (name "Net-(Q3-G)") (class "Default")
      (node (ref "Q3") (pin "1") (pinfunction "G_1") (pintype "passive"))
      (node (ref "R12") (pin "2") (pinfunction "2_2") (pintype "passive"))
    )
    (net (code "141") (name "Net-(Q4-D)") (class "Default")
      (node (ref "Q4") (pin "3") (pinfunction "D_3") (pintype "passive"))
      (node (ref "R14") (pin "P$1") (pinfunction "1_P$1") (pintype "passive"))
      (node (ref "R15") (pin "1") (pinfunction "1_1") (pintype "passive"))
    )
    (net (code "142") (name "Net-(Q4-G)") (class "Default")
      (node (ref "Q4") (pin "1") (pinfunction "G_1") (pintype "passive"))
      (node (ref "R16") (pin "2") (pinfunction "2_2") (pintype "passive"))
    )
    (net (code "143") (name "Net-(Q5-D)") (class "Default")
      (node (ref "Q5") (pin "3") (pinfunction "D_3") (pintype "passive"))
      (node (ref "R18") (pin "P$1") (pinfunction "1_P$1") (pintype "passive"))
      (node (ref "R19") (pin "1") (pinfunction "1_1") (pintype "passive"))
    )
    (net (code "144") (name "Net-(Q5-G)") (class "Default")
      (node (ref "Q5") (pin "1") (pinfunction "G_1") (pintype "passive"))
      (node (ref "R20") (pin "2") (pinfunction "2_2") (pintype "passive"))
    )
    (net (code "145") (name "Net-(Q6-D)") (class "Default")
      (node (ref "Q6") (pin "3") (pinfunction "D_3") (pintype "passive"))
      (node (ref "R22") (pin "P$1") (pinfunction "1_P$1") (pintype "passive"))
      (node (ref "R23") (pin "1") (pinfunction "1_1") (pintype "passive"))
    )
    (net (code "146") (name "Net-(Q6-G)") (class "Default")
      (node (ref "Q6") (pin "1") (pinfunction "G_1") (pintype "passive"))
      (node (ref "R24") (pin "2") (pinfunction "2_2") (pintype "passive"))
    )
    (net (code "147") (name "Net-(Q7-D)") (class "Default")
      (node (ref "Q7") (pin "3") (pinfunction "D_3") (pintype "passive"))
      (node (ref "R26") (pin "P$1") (pinfunction "1_P$1") (pintype "passive"))
      (node (ref "R27") (pin "1") (pinfunction "1_1") (pintype "passive"))
    )
    (net (code "148") (name "Net-(Q7-G)") (class "Default")
      (node (ref "Q7") (pin "1") (pinfunction "G_1") (pintype "passive"))
      (node (ref "R28") (pin "2") (pinfunction "2_2") (pintype "passive"))
    )
    (net (code "149") (name "Net-(Q8-D)") (class "Default")
      (node (ref "Q8") (pin "3") (pinfunction "D_3") (pintype "passive"))
      (node (ref "R30") (pin "P$1") (pinfunction "1_P$1") (pintype "passive"))
      (node (ref "R31") (pin "1") (pinfunction "1_1") (pintype "passive"))
    )
    (net (code "150") (name "Net-(Q8-G)") (class "Default")
      (node (ref "Q8") (pin "1") (pinfunction "G_1") (pintype "passive"))
      (node (ref "R32") (pin "2") (pinfunction "2_2") (pintype "passive"))
    )
    (net (code "151") (name "Net-(Q9-G)") (class "Default")
      (node (ref "Q9") (pin "1") (pinfunction "G_1") (pintype "bidirectional"))
      (node (ref "U$12") (pin "P$7") (pinfunction "TG_P$7") (pintype "bidirectional"))
    )
    (net (code "152") (name "Net-(Q9-S)") (class "Default")
      (node (ref "C15") (pin "2") (pinfunction "2_2") (pintype "passive"))
      (node (ref "Q9") (pin "3") (pinfunction "S_3") (pintype "bidirectional"))
      (node (ref "U$12") (pin "P$8") (pinfunction "TS_P$8") (pintype "bidirectional"))
      (node (ref "U$5") (pin "P$2") (pinfunction "2_P$2") (pintype "passive"))
      (node (ref "U$9") (pin "P$2") (pinfunction "C_P$2") (pintype "passive"))
    )
    (net (code "153") (name "Net-(Q12-D)") (class "Default")
      (node (ref "Q12") (pin "3") (pinfunction "D_3") (pintype "passive"))
      (node (ref "X1") (pin "1") (pinfunction "S_1") (pintype "passive"))
    )
    (net (code "154") (name "Net-(Q13-D)") (class "Default")
      (node (ref "Q13") (pin "3") (pinfunction "D_3") (pintype "passive"))
      (node (ref "X2") (pin "1") (pinfunction "S_1") (pintype "passive"))
    )
    (net (code "155") (name "Net-(Q14-D)") (class "Default")
      (node (ref "Q14") (pin "3") (pinfunction "D_3") (pintype "passive"))
      (node (ref "X3") (pin "1") (pinfunction "S_1") (pintype "passive"))
    )
    (net (code "156") (name "Net-(Q15-D)") (class "Default")
      (node (ref "Q15") (pin "3") (pinfunction "D_3") (pintype "passive"))
      (node (ref "X4") (pin "1") (pinfunction "S_1") (pintype "passive"))
    )
    (net (code "157") (name "Net-(S1-P)") (class "Default")
      (node (ref "F1") (pin "1") (pinfunction "1_1") (pintype "bidirectional"))
      (node (ref "S1") (pin "2") (pinfunction "P_2") (pintype "passive"))
    )
    (net (code "158") (name "Net-(THERM_1A-S)") (class "Default")
      (node (ref "R33") (pin "2") (pinfunction "2_2") (pintype "passive"))
      (node (ref "R34") (pin "2") (pinfunction "2_2") (pintype "passive"))
      (node (ref "THERM_1") (pin "1") (pinfunction "S_1") (pintype "passive"))
    )
    (net (code "159") (name "Net-(THERM_2A-S)") (class "Default")
      (node (ref "R35") (pin "2") (pinfunction "2_2") (pintype "passive"))
      (node (ref "R36") (pin "2") (pinfunction "2_2") (pintype "passive"))
      (node (ref "THERM_2") (pin "1") (pinfunction "S_1") (pintype "passive"))
    )
    (net (code "160") (name "Net-(U$1-S1)") (class "Default")
      (node (ref "R4") (pin "1") (pinfunction "1_1") (pintype "passive"))
      (node (ref "U$1") (pin "25") (pinfunction "S1_25") (pintype "bidirectional"))
    )
    (net (code "161") (name "Net-(U$1-V+)") (class "Default")
      (node (ref "C13") (pin "1") (pinfunction "1_1") (pintype "passive"))
      (node (ref "R37") (pin "1") (pinfunction "1_1") (pintype "passive"))
      (node (ref "U$1") (pin "1") (pinfunction "V+_1") (pintype "bidirectional"))
    )
    (net (code "162") (name "Net-(U$5-1)") (class "Default")
      (node (ref "U$3") (pin "+") (pinfunction "+_+") (pintype "passive"))
      (node (ref "U$4") (pin "5_1") (pinfunction "IP-_5_1") (pintype "bidirectional"))
      (node (ref "U$4") (pin "5_10") (pinfunction "IP-_5_10") (pintype "bidirectional"))
      (node (ref "U$4") (pin "5_11") (pinfunction "IP-_5_11") (pintype "bidirectional"))
      (node (ref "U$4") (pin "5_12") (pinfunction "IP-_5_12") (pintype "bidirectional"))
      (node (ref "U$4") (pin "5_13") (pinfunction "IP-_5_13") (pintype "bidirectional"))
      (node (ref "U$4") (pin "5_14") (pinfunction "IP-_5_14") (pintype "bidirectional"))
      (node (ref "U$4") (pin "5_15") (pinfunction "IP-_5_15") (pintype "bidirectional"))
      (node (ref "U$4") (pin "5_16") (pinfunction "IP-_5_16") (pintype "bidirectional"))
      (node (ref "U$4") (pin "5_2") (pinfunction "IP-_5_2") (pintype "bidirectional"))
      (node (ref "U$4") (pin "5_3") (pinfunction "IP-_5_3") (pintype "bidirectional"))
      (node (ref "U$4") (pin "5_4") (pinfunction "IP-_5_4") (pintype "bidirectional"))
      (node (ref "U$4") (pin "5_5") (pinfunction "IP-_5_5") (pintype "bidirectional"))
      (node (ref "U$4") (pin "5_6") (pinfunction "IP-_5_6") (pintype "bidirectional"))
      (node (ref "U$4") (pin "5_7") (pinfunction "IP-_5_7") (pintype "bidirectional"))
      (node (ref "U$4") (pin "5_8") (pinfunction "IP-_5_8") (pintype "bidirectional"))
      (node (ref "U$4") (pin "5_9") (pinfunction "IP-_5_9") (pintype "bidirectional"))
      (node (ref "U$4") (pin "5_B") (pinfunction "IP-_5_B") (pintype "bidirectional"))
      (node (ref "U$4") (pin "5_T") (pinfunction "IP-_5_T") (pintype "bidirectional"))
      (node (ref "U$5") (pin "P$1") (pinfunction "1_P$1") (pintype "passive"))
      (node (ref "U$6") (pin "+") (pinfunction "+_+") (pintype "passive"))
      (node (ref "U$7") (pin "+") (pinfunction "+_+") (pintype "passive"))
    )
    (net (code "163") (name "unconnected-(IC2-DRAIN10-PadP$17)") (class "Default")
      (node (ref "IC2") (pin "P$17") (pinfunction "DRAIN10_P$17") (pintype "bidirectional"))
    )
    (net (code "164") (name "unconnected-(IC2-DRAIN11-PadP$18)") (class "Default")
      (node (ref "IC2") (pin "P$18") (pinfunction "DRAIN11_P$18") (pintype "bidirectional"))
    )
    (net (code "165") (name "unconnected-(IC2-SER_OUT-PadP$11)") (class "Default")
      (node (ref "IC2") (pin "P$11") (pinfunction "SER_OUT_P$11") (pintype "bidirectional"))
    )
    (net (code "166") (name "unconnected-(U$1-MMB-Pad33)") (class "Default")
      (node (ref "U$1") (pin "33") (pinfunction "MMB_33") (pintype "bidirectional"))
    )
    (net (code "167") (name "unconnected-(U$1-NC-Pad27)") (class "Default")
      (node (ref "U$1") (pin "27") (pinfunction "NC_27") (pintype "bidirectional"))
    )
    (net (code "168") (name "unconnected-(U$1-S9-Pad9)") (class "Default")
      (node (ref "U$1") (pin "9") (pinfunction "S9_9") (pintype "bidirectional"))
    )
    (net (code "169") (name "unconnected-(U$1-S10-Pad7)") (class "Default")
      (node (ref "U$1") (pin "7") (pinfunction "S10_7") (pintype "bidirectional"))
    )
    (net (code "170") (name "unconnected-(U$1-S11-Pad5)") (class "Default")
      (node (ref "U$1") (pin "5") (pinfunction "S11_5") (pintype "bidirectional"))
    )
    (net (code "171") (name "unconnected-(U$1-S12-Pad3)") (class "Default")
      (node (ref "U$1") (pin "3") (pinfunction "S12_3") (pintype "bidirectional"))
    )
    (net (code "172") (name "unconnected-(U$1-WDTB-Pad34)") (class "Default")
      (node (ref "U$1") (pin "34") (pinfunction "WDTB_34") (pintype "bidirectional"))
    )
    (net (code "173") (name "unconnected-(U$8-FAULT-Pad3)") (class "Default")
      (node (ref "U$8") (pin "3") (pinfunction "FAULT_3") (pintype "bidirectional"))
    )
    (net (code "174") (name "unconnected-(U$8-TIMER-Pad2)") (class "Default")
      (node (ref "U$8") (pin "2") (pinfunction "TIMER_2") (pintype "bidirectional"))
    )
    (net (code "175") (name "unconnected-(U$13-P6.7-Pad6.7)") (class "Default")
      (node (ref "U$13") (pin "6.7") (pinfunction "P6.7_6.7") (pintype "bidirectional"))
    )
    (net (code "176") (name "unconnected-(U$13-P7.0-Pad7.0)") (class "Default")
      (node (ref "U$13") (pin "7.0") (pinfunction "P7.0_7.0") (pintype "bidirectional"))
    )
    (net (code "177") (name "unconnected-(U$13-P7.1-Pad7.1)") (class "Default")
      (node (ref "U$13") (pin "7.1") (pinfunction "P7.1_7.1") (pintype "bidirectional"))
    )
    (net (code "178") (name "unconnected-(U$13-P7.2-Pad7.2)") (class "Default")
      (node (ref "U$13") (pin "7.2") (pinfunction "P7.2_7.2") (pintype "bidirectional"))
    )
    (net (code "179") (name "unconnected-(U$13-P7.3-Pad7.3)") (class "Default")
      (node (ref "U$13") (pin "7.3") (pinfunction "P7.3_7.3") (pintype "bidirectional"))
    )
    (net (code "180") (name "unconnected-(U$13-P7.4-Pad7.4)") (class "Default")
      (node (ref "U$13") (pin "7.4") (pinfunction "P7.4_7.4") (pintype "bidirectional"))
    )
    (net (code "181") (name "unconnected-(U$13-P7.5-Pad7.5)") (class "Default")
      (node (ref "U$13") (pin "7.5") (pinfunction "P7.5_7.5") (pintype "bidirectional"))
    )
    (net (code "182") (name "unconnected-(U$13-P7.6-Pad7.6)") (class "Default")
      (node (ref "U$13") (pin "7.6") (pinfunction "P7.6_7.6") (pintype "bidirectional"))
    )
    (net (code "183") (name "unconnected-(U$13-P7.7-Pad7.7)") (class "Default")
      (node (ref "U$13") (pin "7.7") (pinfunction "P7.7_7.7") (pintype "bidirectional"))
    )
    (net (code "184") (name "unconnected-(U$13-P8.2-Pad8.2)") (class "Default")
      (node (ref "U$13") (pin "8.2") (pinfunction "P8.2_8.2") (pintype "bidirectional"))
    )
    (net (code "185") (name "unconnected-(U$13-P8.3-Pad8.3)") (class "Default")
      (node (ref "U$13") (pin "8.3") (pinfunction "P8.3_8.3") (pintype "bidirectional"))
    )
    (net (code "186") (name "unconnected-(U$13-P8.4-Pad8.4)") (class "Default")
      (node (ref "U$13") (pin "8.4") (pinfunction "P8.4_8.4") (pintype "bidirectional"))
    )
    (net (code "187") (name "unconnected-(U$13-P8.5-Pad8.5)") (class "Default")
      (node (ref "U$13") (pin "8.5") (pinfunction "P8.5_8.5") (pintype "bidirectional"))
    )
    (net (code "188") (name "unconnected-(U$13-P8.6-Pad8.6)") (class "Default")
      (node (ref "U$13") (pin "8.6") (pinfunction "P8.6_8.6") (pintype "bidirectional"))
    )
    (net (code "189") (name "unconnected-(U$13-P8.7-Pad8.7)") (class "Default")
      (node (ref "U$13") (pin "8.7") (pinfunction "P8.7_8.7") (pintype "bidirectional"))
    )
    (net (code "190") (name "unconnected-(U$13-P9.1-Pad9.1)") (class "Default")
      (node (ref "U$13") (pin "9.1") (pinfunction "P9.1_9.1") (pintype "bidirectional"))
    )
    (net (code "191") (name "unconnected-(U$13-P9.2-Pad9.2)") (class "Default")
      (node (ref "U$13") (pin "9.2") (pinfunction "P9.2_9.2") (pintype "bidirectional"))
    )
    (net (code "192") (name "unconnected-(U$13-P9.3-Pad9.3)") (class "Default")
      (node (ref "U$13") (pin "9.3") (pinfunction "P9.3_9.3") (pintype "bidirectional"))
    )
    (net (code "193") (name "unconnected-(U$13-P10.4-Pad10.4)") (class "Default")
      (node (ref "U$13") (pin "10.4") (pinfunction "P10.4_10.4") (pintype "bidirectional"))
    )
    (net (code "194") (name "unconnected-(U$13-P10.5-Pad10.5)") (class "Default")
      (node (ref "U$13") (pin "10.5") (pinfunction "P10.5_10.5") (pintype "bidirectional"))
    )
    (net (code "195") (name "unconnected-(U$13-{slash}RST-PadRST)") (class "Default")
      (node (ref "U$13") (pin "RST") (pinfunction "/RST_RST") (pintype "bidirectional"))
    )
    (net (code "196") (name "unconnected-(U1-A0-Pad31)") (class "Default")
      (node (ref "U1") (pin "31") (pinfunction "A0_31") (pintype "bidirectional"))
    )
    (net (code "197") (name "unconnected-(U1-A1-Pad32)") (class "Default")
      (node (ref "U1") (pin "32") (pinfunction "A1_32") (pintype "bidirectional"))
    )
    (net (code "198") (name "unconnected-(U1-A2-Pad33)") (class "Default")
      (node (ref "U1") (pin "33") (pinfunction "A2_33") (pintype "bidirectional"))
    )
    (net (code "199") (name "unconnected-(U1-A3-Pad34)") (class "Default")
      (node (ref "U1") (pin "34") (pinfunction "A3_34") (pintype "bidirectional"))
    )
    (net (code "200") (name "unconnected-(U1-A4-Pad35)") (class "Default")
      (node (ref "U1") (pin "35") (pinfunction "A4_35") (pintype "bidirectional"))
    )
    (net (code "201") (name "unconnected-(U1-A5-Pad36)") (class "Default")
      (node (ref "U1") (pin "36") (pinfunction "A5_36") (pintype "bidirectional"))
    )
    (net (code "202") (name "unconnected-(U1-A6-Pad37)") (class "Default")
      (node (ref "U1") (pin "37") (pinfunction "A6_37") (pintype "bidirectional"))
    )
    (net (code "203") (name "unconnected-(U1-A7-Pad38)") (class "Default")
      (node (ref "U1") (pin "38") (pinfunction "A7_38") (pintype "bidirectional"))
    )
    (net (code "204") (name "unconnected-(U1-A8-Pad13)") (class "Default")
      (node (ref "U1") (pin "13") (pinfunction "A8_13") (pintype "bidirectional"))
    )
    (net (code "205") (name "unconnected-(U1-A9-Pad14)") (class "Default")
      (node (ref "U1") (pin "14") (pinfunction "A9_14") (pintype "bidirectional"))
    )
    (net (code "206") (name "unconnected-(U1-A10-Pad15)") (class "Default")
      (node (ref "U1") (pin "15") (pinfunction "A10_15") (pintype "bidirectional"))
    )
    (net (code "207") (name "unconnected-(U1-A11-Pad16)") (class "Default")
      (node (ref "U1") (pin "16") (pinfunction "A11_16") (pintype "bidirectional"))
    )
    (net (code "208") (name "unconnected-(U1-A12-Pad17)") (class "Default")
      (node (ref "U1") (pin "17") (pinfunction "A12_17") (pintype "bidirectional"))
    )
    (net (code "209") (name "unconnected-(U1-A13-Pad18)") (class "Default")
      (node (ref "U1") (pin "18") (pinfunction "A13_18") (pintype "bidirectional"))
    )
    (net (code "210") (name "unconnected-(U1-A14-Pad19)") (class "Default")
      (node (ref "U1") (pin "19") (pinfunction "A14_19") (pintype "bidirectional"))
    )
    (net (code "211") (name "unconnected-(U1-D0-Pad4)") (class "Default")
      (node (ref "U1") (pin "4") (pinfunction "D0_4") (pintype "bidirectional"))
    )
    (net (code "212") (name "unconnected-(U1-D1-Pad3)") (class "Default")
      (node (ref "U1") (pin "3") (pinfunction "D1_3") (pintype "bidirectional"))
    )
    (net (code "213") (name "unconnected-(U1-D2-Pad6)") (class "Default")
      (node (ref "U1") (pin "6") (pinfunction "D2_6") (pintype "bidirectional"))
    )
    (net (code "214") (name "unconnected-(U1-D3-Pad5)") (class "Default")
      (node (ref "U1") (pin "5") (pinfunction "D3_5") (pintype "bidirectional"))
    )
    (net (code "215") (name "unconnected-(U1-D4-Pad8)") (class "Default")
      (node (ref "U1") (pin "8") (pinfunction "D4_8") (pintype "bidirectional"))
    )
    (net (code "216") (name "unconnected-(U1-D5-Pad7)") (class "Default")
      (node (ref "U1") (pin "7") (pinfunction "D5_7") (pintype "bidirectional"))
    )
    (net (code "217") (name "unconnected-(U1-D6-Pad10)") (class "Default")
      (node (ref "U1") (pin "10") (pinfunction "D6_10") (pintype "bidirectional"))
    )
    (net (code "218") (name "unconnected-(U1-D7-Pad9)") (class "Default")
      (node (ref "U1") (pin "9") (pinfunction "D7_9") (pintype "bidirectional"))
    )
    (net (code "219") (name "unconnected-(U1-{slash}CS-Pad27)") (class "Default")
      (node (ref "U1") (pin "27") (pinfunction "/CS_27") (pintype "bidirectional"))
    )
    (net (code "220") (name "unconnected-(U1-{slash}RD-Pad26)") (class "Default")
      (node (ref "U1") (pin "26") (pinfunction "/RD_26") (pintype "bidirectional"))
    )
    (net (code "221") (name "unconnected-(U1-{slash}WR-Pad25)") (class "Default")
      (node (ref "U1") (pin "25") (pinfunction "/WR_25") (pintype "bidirectional"))
    )
  )
)
